# S7G7_footprint_simplified_w_ethernet_v1p.net
KiCad netlist of a schematic drawn in EAGLE
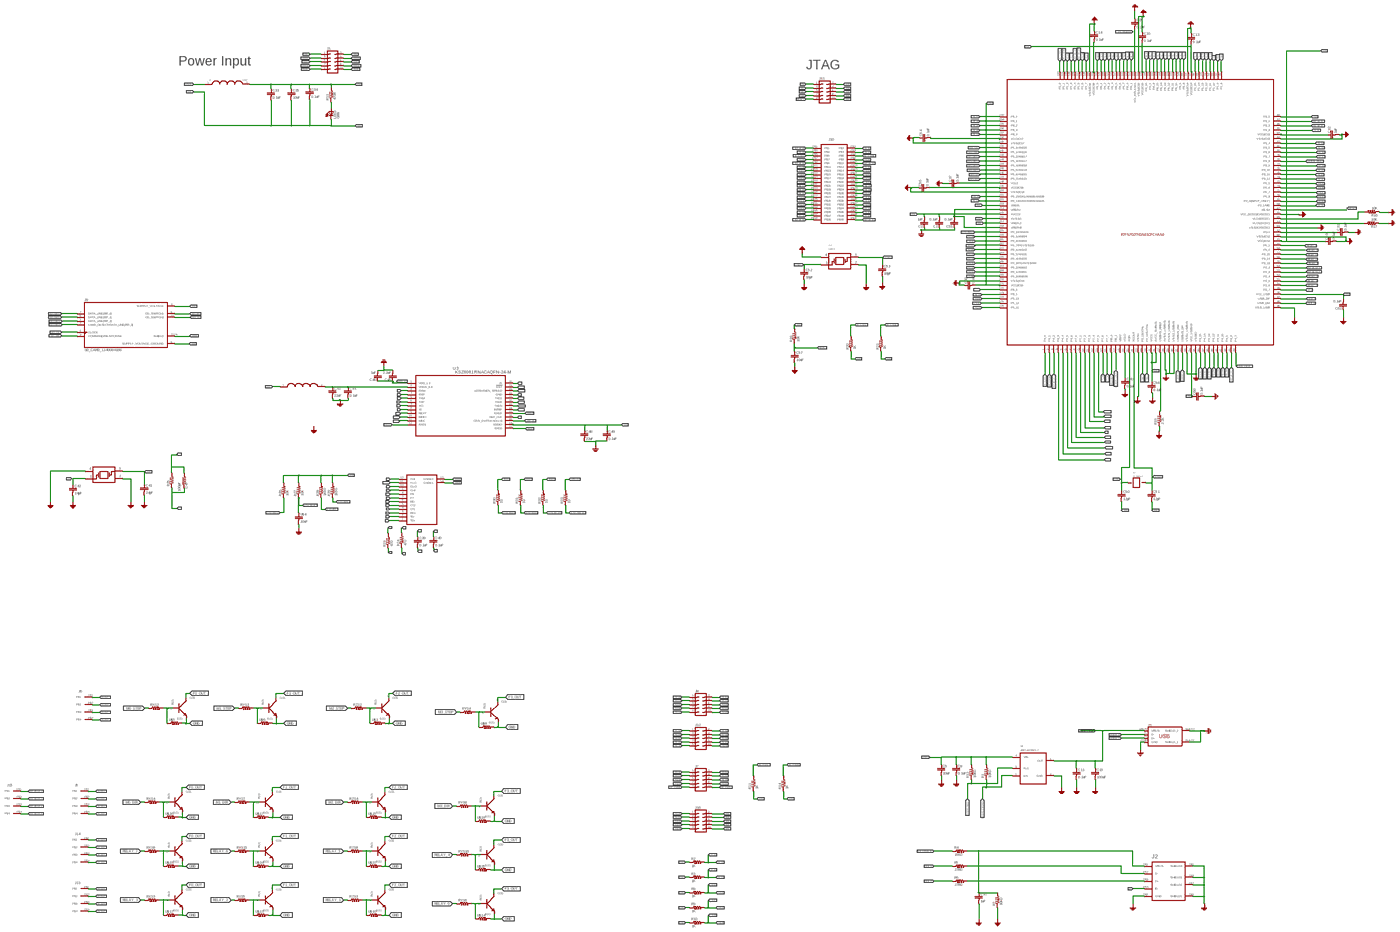
[diagram p0: schematic, sheet 1, overview]
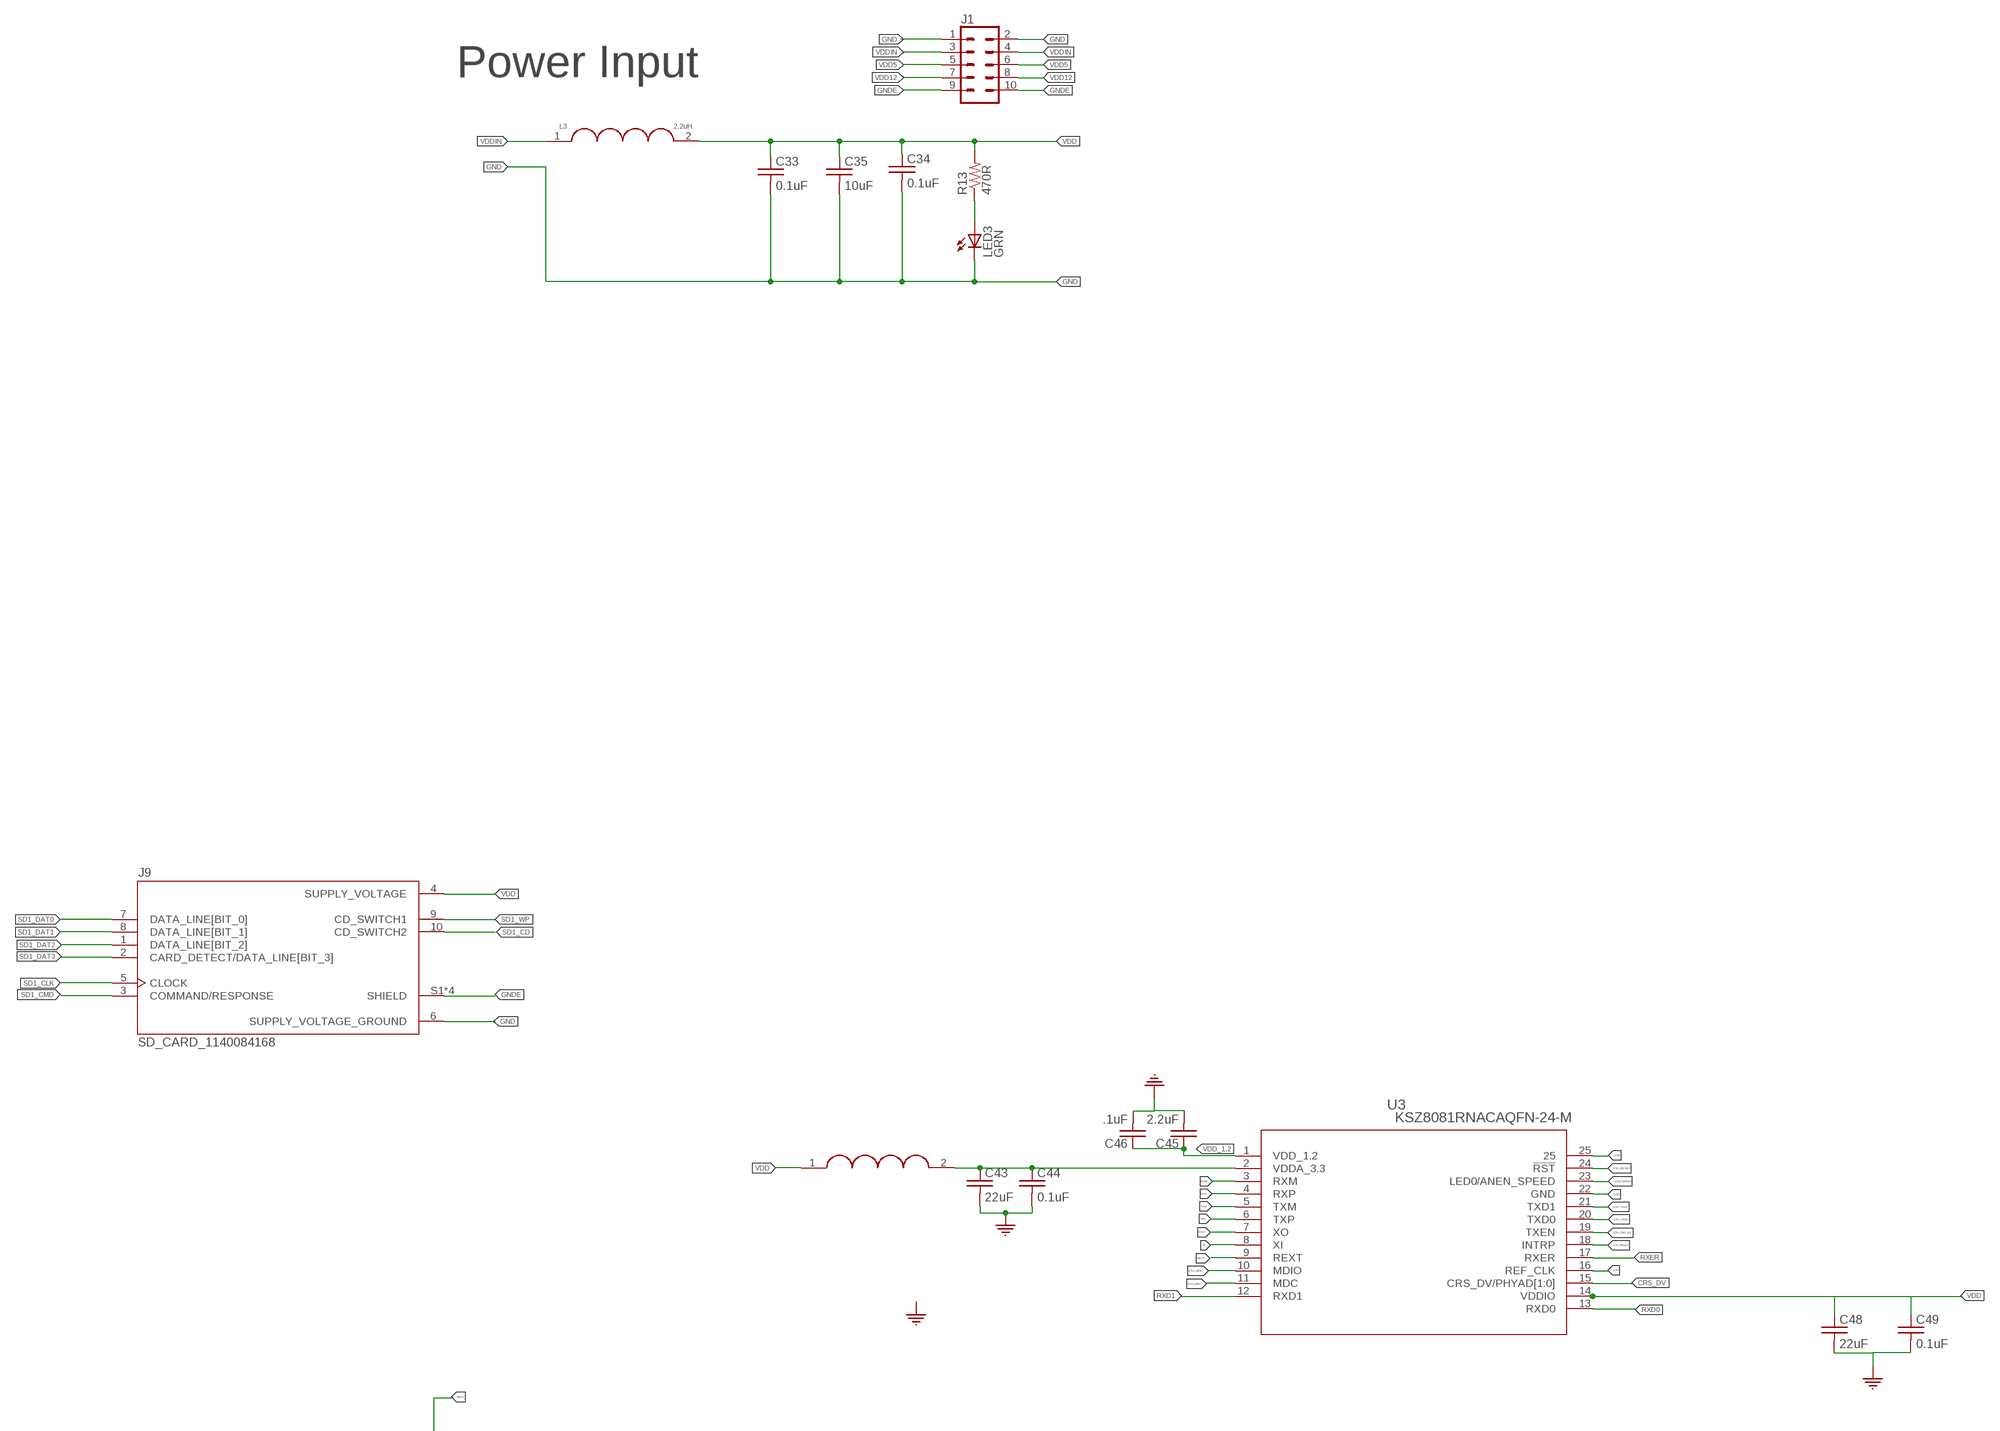
[diagram p1: schematic, sheet 1, part 1 of 4]
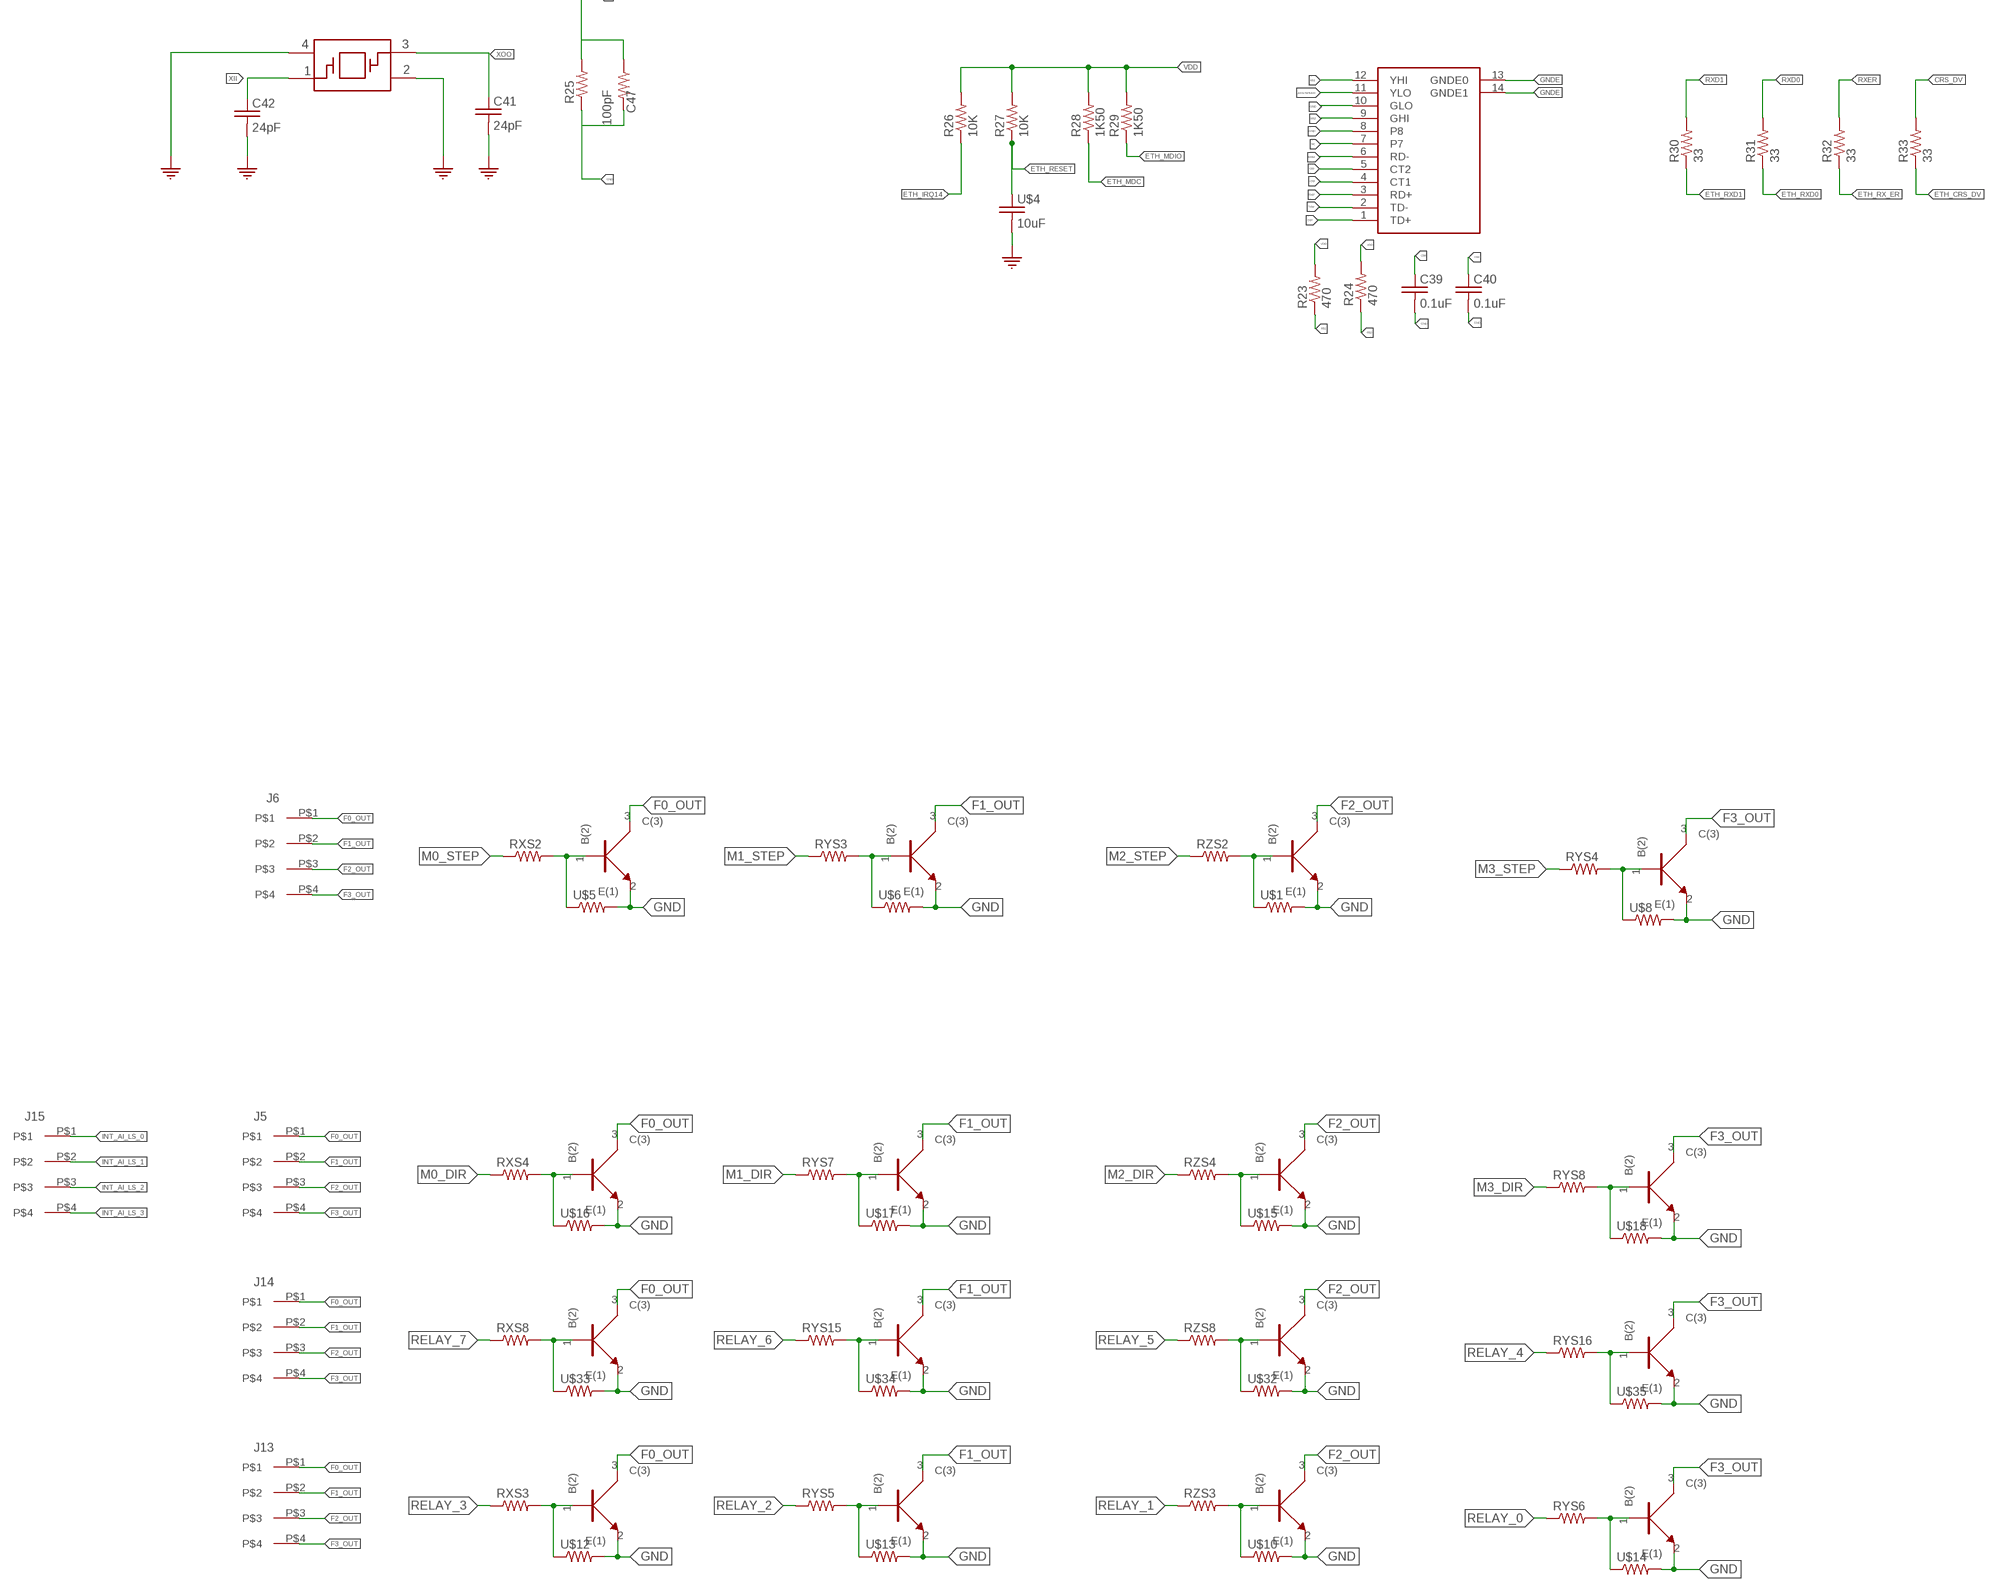
[diagram p2: schematic, sheet 1, part 2 of 4]
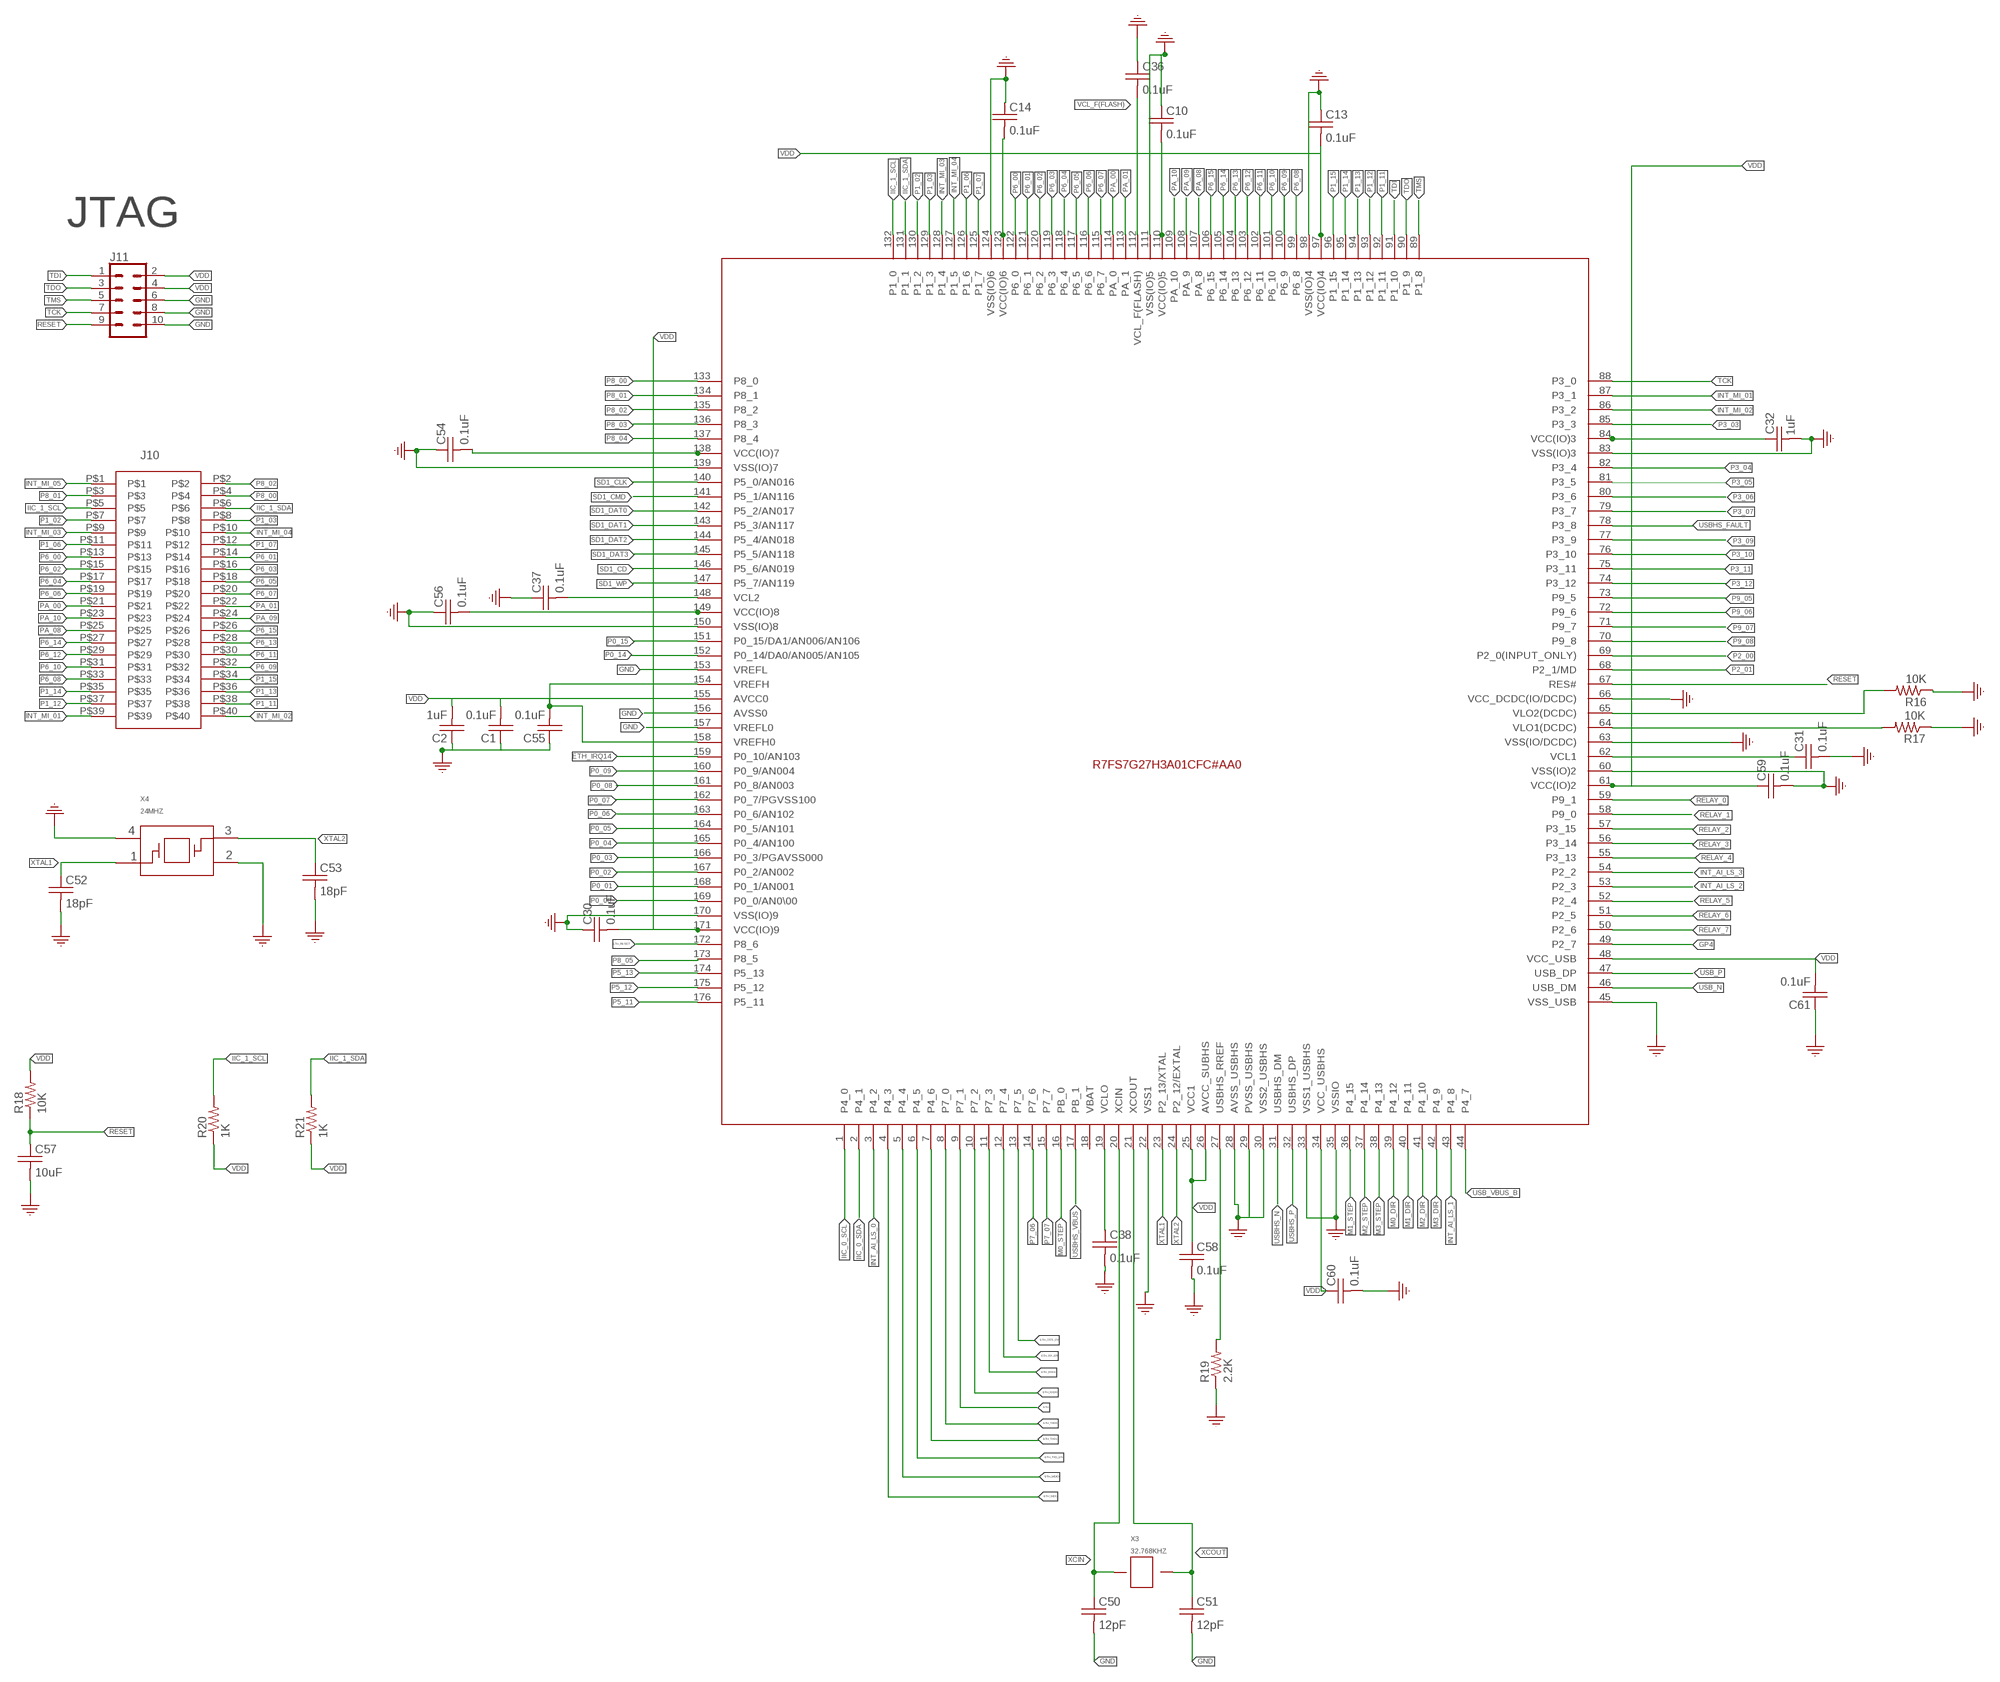
[diagram p3: schematic, sheet 1, part 3 of 4]
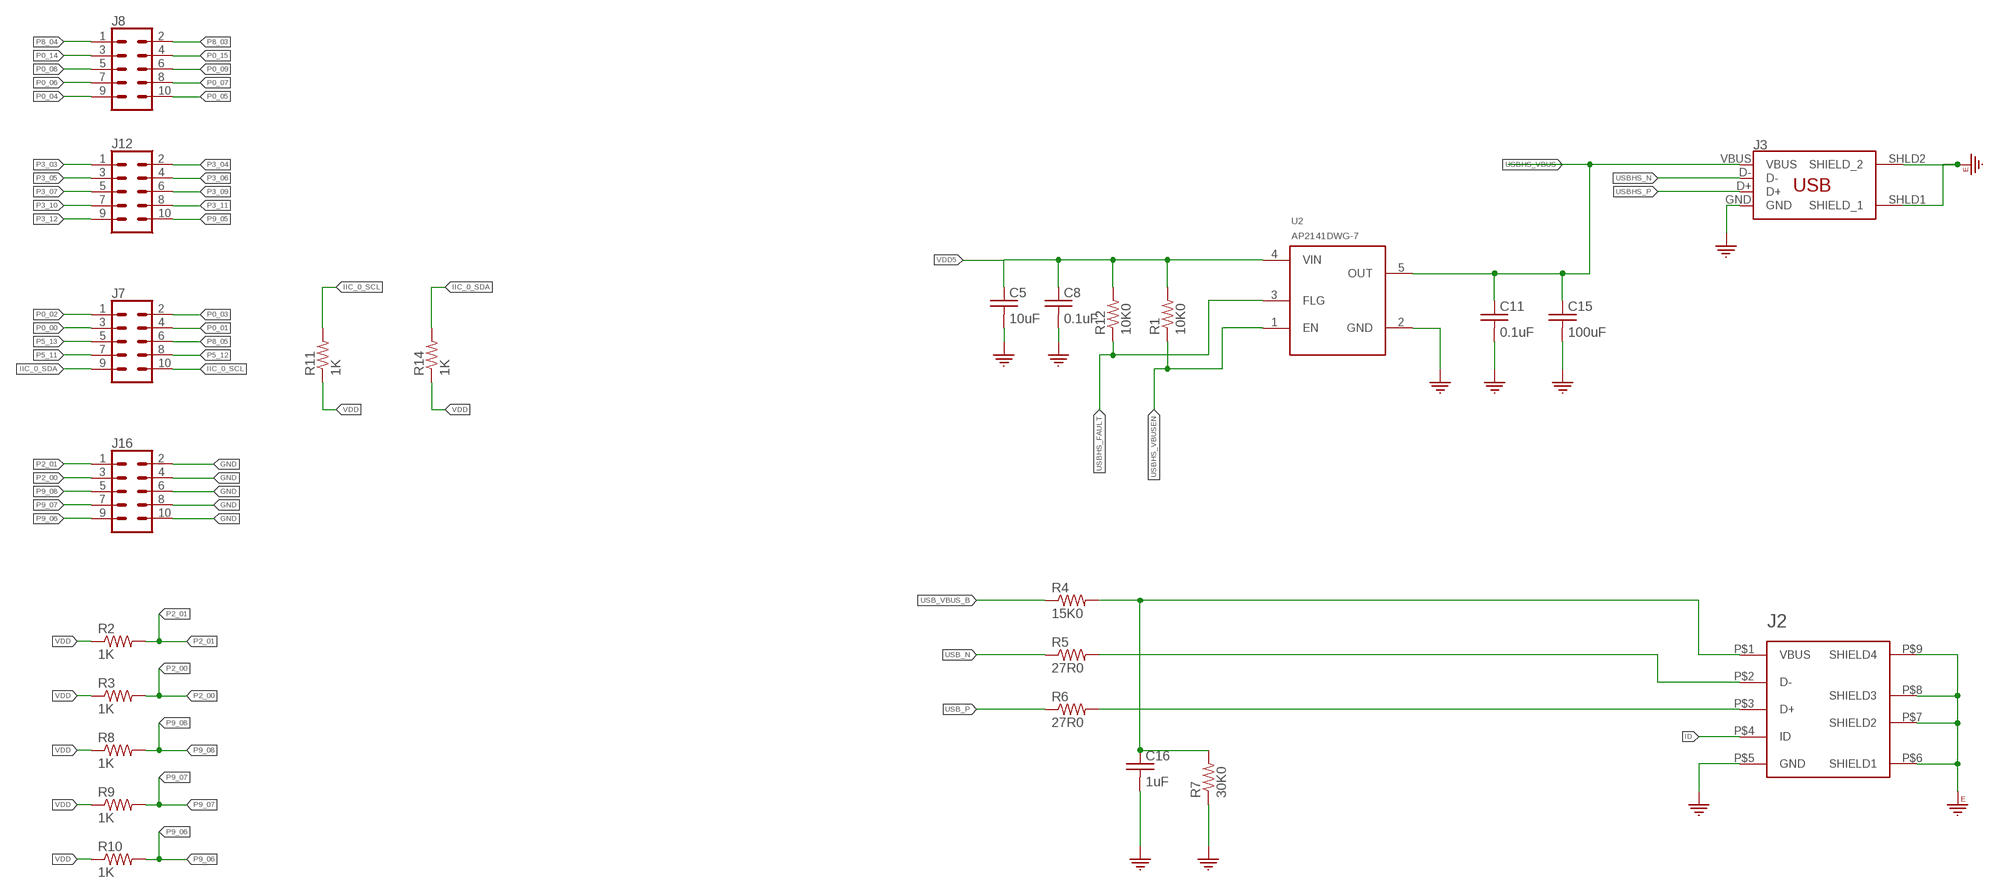
[diagram p4: schematic, sheet 1, part 4 of 4]

(export (version "E")
  (design (tool "Eeschema 10.0.6"))
  (components
    (comp (ref "C1")
      (value "0.1uF")
      (footprint "eagle-import:0402")
      (libsource (lib "eagle-import") (part "C_0402"))
    )
    (comp (ref "C2")
      (value "1uF")
      (footprint "eagle-import:0402")
      (libsource (lib "eagle-import") (part "C_0402"))
    )
    (comp (ref "C5")
      (value "10uF")
      (footprint "eagle-import:0402")
      (libsource (lib "eagle-import") (part "C_0402"))
    )
    (comp (ref "C8")
      (value "0.1uF")
      (footprint "eagle-import:0402")
      (libsource (lib "eagle-import") (part "C_0402"))
    )
    (comp (ref "C10")
      (value "0.1uF")
      (footprint "eagle-import:0402")
      (libsource (lib "eagle-import") (part "C_0402"))
    )
    (comp (ref "C11")
      (value "0.1uF")
      (footprint "eagle-import:0402")
      (libsource (lib "eagle-import") (part "C_0402"))
    )
    (comp (ref "C13")
      (value "0.1uF")
      (footprint "eagle-import:0402")
      (libsource (lib "eagle-import") (part "C_0402"))
    )
    (comp (ref "C14")
      (value "0.1uF")
      (footprint "eagle-import:0402")
      (libsource (lib "eagle-import") (part "C_0402"))
    )
    (comp (ref "C15")
      (value "100uF")
      (footprint "eagle-import:C1210")
      (libsource (lib "eagle-import") (part "C_1210"))
    )
    (comp (ref "C16")
      (value "1uF")
      (footprint "eagle-import:0402")
      (libsource (lib "eagle-import") (part "C_0402"))
    )
    (comp (ref "C30")
      (value "0.1uF")
      (footprint "eagle-import:0402")
      (libsource (lib "eagle-import") (part "C_0402"))
    )
    (comp (ref "C31")
      (value "0.1uF")
      (footprint "eagle-import:0402")
      (libsource (lib "eagle-import") (part "C_0402"))
    )
    (comp (ref "C32")
      (value "1uF")
      (footprint "eagle-import:0402")
      (libsource (lib "eagle-import") (part "C_0402"))
    )
    (comp (ref "C33")
      (value "0.1uF")
      (footprint "eagle-import:0402")
      (libsource (lib "eagle-import") (part "C_0402"))
    )
    (comp (ref "C34")
      (value "0.1uF")
      (footprint "eagle-import:0402")
      (libsource (lib "eagle-import") (part "C_0402"))
    )
    (comp (ref "C35")
      (value "10uF")
      (footprint "eagle-import:0402")
      (libsource (lib "eagle-import") (part "C_0402"))
    )
    (comp (ref "C36")
      (value "0.1uF")
      (footprint "eagle-import:0402")
      (libsource (lib "eagle-import") (part "C_0402"))
    )
    (comp (ref "C37")
      (value "0.1uF")
      (footprint "eagle-import:0402")
      (libsource (lib "eagle-import") (part "C_0402"))
    )
    (comp (ref "C38")
      (value "0.1uF")
      (footprint "eagle-import:0402")
      (libsource (lib "eagle-import") (part "C_0402"))
    )
    (comp (ref "C39")
      (value "0.1uF")
      (footprint "eagle-import:0402")
      (libsource (lib "eagle-import") (part "C_0402"))
    )
    (comp (ref "C40")
      (value "0.1uF")
      (footprint "eagle-import:0402")
      (libsource (lib "eagle-import") (part "C_0402"))
    )
    (comp (ref "C41")
      (value "24pF")
      (footprint "eagle-import:0402")
      (libsource (lib "eagle-import") (part "C_0402"))
    )
    (comp (ref "C42")
      (value "24pF")
      (footprint "eagle-import:0402")
      (libsource (lib "eagle-import") (part "C_0402"))
    )
    (comp (ref "C43")
      (value "22uF")
      (footprint "eagle-import:0603")
      (libsource (lib "eagle-import") (part "C_0603"))
    )
    (comp (ref "C44")
      (value "0.1uF")
      (footprint "eagle-import:0402")
      (libsource (lib "eagle-import") (part "C_0402"))
    )
    (comp (ref "C45")
      (value "2.2uF")
      (footprint "eagle-import:0402")
      (libsource (lib "eagle-import") (part "C_0402"))
    )
    (comp (ref "C46")
      (value ".1uF")
      (footprint "eagle-import:0402")
      (libsource (lib "eagle-import") (part "C_0402"))
    )
    (comp (ref "C47")
      (value "100pF")
      (footprint "eagle-import:0402")
      (libsource (lib "eagle-import") (part "R_0402"))
    )
    (comp (ref "C48")
      (value "22uF")
      (footprint "eagle-import:0603")
      (libsource (lib "eagle-import") (part "C_0603"))
    )
    (comp (ref "C49")
      (value "0.1uF")
      (footprint "eagle-import:0402")
      (libsource (lib "eagle-import") (part "C_0402"))
    )
    (comp (ref "C50")
      (value "12pF")
      (footprint "eagle-import:0402")
      (libsource (lib "eagle-import") (part "C_0402"))
    )
    (comp (ref "C51")
      (value "12pF")
      (footprint "eagle-import:0402")
      (libsource (lib "eagle-import") (part "C_0402"))
    )
    (comp (ref "C52")
      (value "18pF")
      (footprint "eagle-import:0402")
      (libsource (lib "eagle-import") (part "C_0402"))
    )
    (comp (ref "C53")
      (value "18pF")
      (footprint "eagle-import:0402")
      (libsource (lib "eagle-import") (part "C_0402"))
    )
    (comp (ref "C54")
      (value "0.1uF")
      (footprint "eagle-import:0402")
      (libsource (lib "eagle-import") (part "C_0402"))
    )
    (comp (ref "C55")
      (value "0.1uF")
      (footprint "eagle-import:0402")
      (libsource (lib "eagle-import") (part "C_0402"))
    )
    (comp (ref "C56")
      (value "0.1uF")
      (footprint "eagle-import:0402")
      (libsource (lib "eagle-import") (part "C_0402"))
    )
    (comp (ref "C57")
      (value "10uF")
      (footprint "eagle-import:0402")
      (libsource (lib "eagle-import") (part "C_0402"))
    )
    (comp (ref "C58")
      (value "0.1uF")
      (footprint "eagle-import:0402")
      (libsource (lib "eagle-import") (part "C_0402"))
    )
    (comp (ref "C59")
      (value "0.1uF")
      (footprint "eagle-import:0402")
      (libsource (lib "eagle-import") (part "C_0402"))
    )
    (comp (ref "C60")
      (value "0.1uF")
      (footprint "eagle-import:0402")
      (libsource (lib "eagle-import") (part "C_0402"))
    )
    (comp (ref "C61")
      (value "0.1uF")
      (footprint "eagle-import:0402")
      (libsource (lib "eagle-import") (part "C_0402"))
    )
    (comp (ref "FB2/2")
      (value "FB_0805_120_OHM")
      (footprint "eagle-import:0805")
      (libsource (lib "eagle-import") (part "FB_0805_120_OHM"))
    )
    (comp (ref "J1")
      (value "CONN_05X2PTH")
      (footprint "eagle-import:2X5")
      (libsource (lib "eagle-import") (part "CONN_05X2PTH"))
    )
    (comp (ref "J2")
      (value "USB_MICRO-B")
      (footprint "eagle-import:USB_MICRO-B")
      (libsource (lib "eagle-import") (part "USB_MICRO-B"))
    )
    (comp (ref "J3")
      (value "USB_A")
      (footprint "eagle-import:USB_A_SMT")
      (libsource (lib "eagle-import") (part "USB_A"))
    )
    (comp (ref "J4")
      (value "RJ45_WITH_ELEC")
      (footprint "eagle-import:RJ45_TH_ELEC")
      (libsource (lib "eagle-import") (part "RJ45_WITH_ELEC"))
    )
    (comp (ref "J5")
      (value "3.81MM_1_X_4_RT_ANGLE_PLUG_HEADER")
      (footprint "eagle-import:1X4_3.81MM_PITCH")
      (libsource (lib "eagle-import") (part "3.81MM_1_X_4_RT_ANGLE_PLUG_HEADER"))
    )
    (comp (ref "J6")
      (value "3.81MM_1_X_4_RT_ANGLE_PLUG_HEADER")
      (footprint "eagle-import:1X4_3.81MM_PITCH")
      (libsource (lib "eagle-import") (part "3.81MM_1_X_4_RT_ANGLE_PLUG_HEADER"))
    )
    (comp (ref "J7")
      (value "CONN_05X2NO_SILK")
      (footprint "eagle-import:2X5_NOSILK")
      (libsource (lib "eagle-import") (part "CONN_05X2NO_SILK"))
    )
    (comp (ref "J8")
      (value "CONN_05X2NO_SILK")
      (footprint "eagle-import:2X5_NOSILK")
      (libsource (lib "eagle-import") (part "CONN_05X2NO_SILK"))
    )
    (comp (ref "J9")
      (value "SD_CARD_1140084168")
      (footprint "eagle-import:AMPHENOL_1140084168")
      (fields
        (field (name "DIGI-KEY_PART_NUMBER") "114-00841-68-1-ND")
        (field (name "MF") "Amphenol ICC")
        (field (name "MP") "114-00841-68")
      )
      (libsource (lib "eagle-import") (part "SD_CARD_1140084168"))
    )
    (comp (ref "J10")
      (value "HEADER_2_X_20_GENERIC")
      (footprint "eagle-import:HEADER_2_X_20_.1_INCH")
      (libsource (lib "eagle-import") (part "HEADER_2_X_20_GENERIC"))
    )
    (comp (ref "J11")
      (value "CONN_05X2PTH")
      (footprint "eagle-import:2X5")
      (libsource (lib "eagle-import") (part "CONN_05X2PTH"))
    )
    (comp (ref "J12")
      (value "CONN_05X2NO_SILK")
      (footprint "eagle-import:2X5_NOSILK")
      (libsource (lib "eagle-import") (part "CONN_05X2NO_SILK"))
    )
    (comp (ref "J13")
      (value "3.81MM_1_X_4_RT_ANGLE_PLUG_HEADER")
      (footprint "eagle-import:1X4_3.81MM_PITCH")
      (libsource (lib "eagle-import") (part "3.81MM_1_X_4_RT_ANGLE_PLUG_HEADER"))
    )
    (comp (ref "J14")
      (value "3.81MM_1_X_4_RT_ANGLE_PLUG_HEADER")
      (footprint "eagle-import:1X4_3.81MM_PITCH")
      (libsource (lib "eagle-import") (part "3.81MM_1_X_4_RT_ANGLE_PLUG_HEADER"))
    )
    (comp (ref "J15")
      (value "3.81MM_1_X_4_RT_ANGLE_PLUG_HEADER")
      (footprint "eagle-import:1X4_3.81MM_PITCH")
      (libsource (lib "eagle-import") (part "3.81MM_1_X_4_RT_ANGLE_PLUG_HEADER"))
    )
    (comp (ref "J16")
      (value "CONN_05X2SHD_SMD")
      (footprint "eagle-import:2X5-SHROUDED_SMD")
      (libsource (lib "eagle-import") (part "CONN_05X2SHD_SMD"))
    )
    (comp (ref "L3")
      (value "2.2uH")
      (footprint "eagle-import:1008_(2520_METRIC)")
      (libsource (lib "eagle-import") (part "INDUCTOR_1008_2.2_MH_1.3A"))
    )
    (comp (ref "LED3")
      (value "LED_0805_GREEN")
      (footprint "eagle-import:LED_0805_GREEN")
      (libsource (lib "eagle-import") (part "LED_0805_GREEN"))
    )
    (comp (ref "R1")
      (value "10K0")
      (footprint "eagle-import:0402")
      (libsource (lib "eagle-import") (part "R_0402"))
    )
    (comp (ref "R2")
      (value "1K")
      (footprint "eagle-import:0402")
      (libsource (lib "eagle-import") (part "R_0402"))
    )
    (comp (ref "R3")
      (value "1K")
      (footprint "eagle-import:0402")
      (libsource (lib "eagle-import") (part "R_0402"))
    )
    (comp (ref "R4")
      (value "15K0")
      (footprint "eagle-import:0402")
      (libsource (lib "eagle-import") (part "R_0402"))
    )
    (comp (ref "R5")
      (value "27R0")
      (footprint "eagle-import:0402")
      (libsource (lib "eagle-import") (part "R_0402"))
    )
    (comp (ref "R6")
      (value "27R0")
      (footprint "eagle-import:0402")
      (libsource (lib "eagle-import") (part "R_0402"))
    )
    (comp (ref "R7")
      (value "30K0")
      (footprint "eagle-import:0402")
      (libsource (lib "eagle-import") (part "R_0402"))
    )
    (comp (ref "R8")
      (value "1K")
      (footprint "eagle-import:0402")
      (libsource (lib "eagle-import") (part "R_0402"))
    )
    (comp (ref "R9")
      (value "1K")
      (footprint "eagle-import:0402")
      (libsource (lib "eagle-import") (part "R_0402"))
    )
    (comp (ref "R10")
      (value "1K")
      (footprint "eagle-import:0402")
      (libsource (lib "eagle-import") (part "R_0402"))
    )
    (comp (ref "R11")
      (value "1K")
      (footprint "eagle-import:0402")
      (libsource (lib "eagle-import") (part "R_0402"))
    )
    (comp (ref "R12")
      (value "10K0")
      (footprint "eagle-import:0402")
      (libsource (lib "eagle-import") (part "R_0402"))
    )
    (comp (ref "R13")
      (value "470R")
      (footprint "eagle-import:0402")
      (libsource (lib "eagle-import") (part "R_0402"))
    )
    (comp (ref "R14")
      (value "1K")
      (footprint "eagle-import:0402")
      (libsource (lib "eagle-import") (part "R_0402"))
    )
    (comp (ref "R16")
      (value "10K")
      (footprint "eagle-import:0402")
      (libsource (lib "eagle-import") (part "R_0402"))
    )
    (comp (ref "R17")
      (value "10K")
      (footprint "eagle-import:0402")
      (libsource (lib "eagle-import") (part "R_0402"))
    )
    (comp (ref "R18")
      (value "10K")
      (footprint "eagle-import:0402")
      (libsource (lib "eagle-import") (part "R_0402"))
    )
    (comp (ref "R19")
      (value "2.2K")
      (footprint "eagle-import:0402")
      (libsource (lib "eagle-import") (part "R_0402"))
    )
    (comp (ref "R20")
      (value "1K")
      (footprint "eagle-import:0402")
      (libsource (lib "eagle-import") (part "R_0402"))
    )
    (comp (ref "R21")
      (value "1K")
      (footprint "eagle-import:0402")
      (libsource (lib "eagle-import") (part "R_0402"))
    )
    (comp (ref "R23")
      (value "470")
      (footprint "eagle-import:0402")
      (libsource (lib "eagle-import") (part "R_0402"))
    )
    (comp (ref "R24")
      (value "470")
      (footprint "eagle-import:0402")
      (libsource (lib "eagle-import") (part "R_0402"))
    )
    (comp (ref "R25")
      (value "6k49")
      (footprint "eagle-import:0402")
      (libsource (lib "eagle-import") (part "R_0402"))
    )
    (comp (ref "R26")
      (value "10K")
      (footprint "eagle-import:0402")
      (libsource (lib "eagle-import") (part "R_0402"))
    )
    (comp (ref "R27")
      (value "10K")
      (footprint "eagle-import:0402")
      (libsource (lib "eagle-import") (part "R_0402"))
    )
    (comp (ref "R28")
      (value "1K50")
      (footprint "eagle-import:0402")
      (libsource (lib "eagle-import") (part "R_0402"))
    )
    (comp (ref "R29")
      (value "1K50")
      (footprint "eagle-import:0402")
      (libsource (lib "eagle-import") (part "R_0402"))
    )
    (comp (ref "R30")
      (value "33")
      (footprint "eagle-import:0402")
      (libsource (lib "eagle-import") (part "R_0402"))
    )
    (comp (ref "R31")
      (value "33")
      (footprint "eagle-import:0402")
      (libsource (lib "eagle-import") (part "R_0402"))
    )
    (comp (ref "R32")
      (value "33")
      (footprint "eagle-import:0402")
      (libsource (lib "eagle-import") (part "R_0402"))
    )
    (comp (ref "R33")
      (value "33")
      (footprint "eagle-import:0402")
      (libsource (lib "eagle-import") (part "R_0402"))
    )
    (comp (ref "RXS2")
      (value "1K")
      (footprint "eagle-import:0402")
      (libsource (lib "eagle-import") (part "R_0402"))
    )
    (comp (ref "RXS3")
      (value "1K")
      (footprint "eagle-import:0402")
      (libsource (lib "eagle-import") (part "R_0402"))
    )
    (comp (ref "RXS4")
      (value "1K")
      (footprint "eagle-import:0402")
      (libsource (lib "eagle-import") (part "R_0402"))
    )
    (comp (ref "RXS8")
      (value "1K")
      (footprint "eagle-import:0402")
      (libsource (lib "eagle-import") (part "R_0402"))
    )
    (comp (ref "RYS3")
      (value "1K")
      (footprint "eagle-import:0402")
      (libsource (lib "eagle-import") (part "R_0402"))
    )
    (comp (ref "RYS4")
      (value "1K")
      (footprint "eagle-import:0402")
      (libsource (lib "eagle-import") (part "R_0402"))
    )
    (comp (ref "RYS5")
      (value "1K")
      (footprint "eagle-import:0402")
      (libsource (lib "eagle-import") (part "R_0402"))
    )
    (comp (ref "RYS6")
      (value "1K")
      (footprint "eagle-import:0402")
      (libsource (lib "eagle-import") (part "R_0402"))
    )
    (comp (ref "RYS7")
      (value "1K")
      (footprint "eagle-import:0402")
      (libsource (lib "eagle-import") (part "R_0402"))
    )
    (comp (ref "RYS8")
      (value "1K")
      (footprint "eagle-import:0402")
      (libsource (lib "eagle-import") (part "R_0402"))
    )
    (comp (ref "RYS15")
      (value "1K")
      (footprint "eagle-import:0402")
      (libsource (lib "eagle-import") (part "R_0402"))
    )
    (comp (ref "RYS16")
      (value "1K")
      (footprint "eagle-import:0402")
      (libsource (lib "eagle-import") (part "R_0402"))
    )
    (comp (ref "RZS2")
      (value "1K")
      (footprint "eagle-import:0402")
      (libsource (lib "eagle-import") (part "R_0402"))
    )
    (comp (ref "RZS3")
      (value "1K")
      (footprint "eagle-import:0402")
      (libsource (lib "eagle-import") (part "R_0402"))
    )
    (comp (ref "RZS4")
      (value "1K")
      (footprint "eagle-import:0402")
      (libsource (lib "eagle-import") (part "R_0402"))
    )
    (comp (ref "RZS8")
      (value "1K")
      (footprint "eagle-import:0402")
      (libsource (lib "eagle-import") (part "R_0402"))
    )
    (comp (ref "U$1")
      (value "1K")
      (footprint "eagle-import:0402")
      (libsource (lib "eagle-import") (part "R_0402"))
    )
    (comp (ref "U$3")
      (value "XTAL_25_MHZ")
      (footprint "eagle-import:SMD_3225")
      (libsource (lib "eagle-import") (part "XTAL_25_MHZ"))
    )
    (comp (ref "U$4")
      (value "10uF")
      (footprint "eagle-import:0402")
      (libsource (lib "eagle-import") (part "C_0402"))
    )
    (comp (ref "U$5")
      (value "1K")
      (footprint "eagle-import:0402")
      (libsource (lib "eagle-import") (part "R_0402"))
    )
    (comp (ref "U$6")
      (value "1K")
      (footprint "eagle-import:0402")
      (libsource (lib "eagle-import") (part "R_0402"))
    )
    (comp (ref "U$8")
      (value "1K")
      (footprint "eagle-import:0402")
      (libsource (lib "eagle-import") (part "R_0402"))
    )
    (comp (ref "U$10")
      (value "1K")
      (footprint "eagle-import:0402")
      (libsource (lib "eagle-import") (part "R_0402"))
    )
    (comp (ref "U$12")
      (value "1K")
      (footprint "eagle-import:0402")
      (libsource (lib "eagle-import") (part "R_0402"))
    )
    (comp (ref "U$13")
      (value "1K")
      (footprint "eagle-import:0402")
      (libsource (lib "eagle-import") (part "R_0402"))
    )
    (comp (ref "U$14")
      (value "1K")
      (footprint "eagle-import:0402")
      (libsource (lib "eagle-import") (part "R_0402"))
    )
    (comp (ref "U$15")
      (value "1K")
      (footprint "eagle-import:0402")
      (libsource (lib "eagle-import") (part "R_0402"))
    )
    (comp (ref "U$16")
      (value "1K")
      (footprint "eagle-import:0402")
      (libsource (lib "eagle-import") (part "R_0402"))
    )
    (comp (ref "U$17")
      (value "1K")
      (footprint "eagle-import:0402")
      (libsource (lib "eagle-import") (part "R_0402"))
    )
    (comp (ref "U$18")
      (value "1K")
      (footprint "eagle-import:0402")
      (libsource (lib "eagle-import") (part "R_0402"))
    )
    (comp (ref "U$32")
      (value "1K")
      (footprint "eagle-import:0402")
      (libsource (lib "eagle-import") (part "R_0402"))
    )
    (comp (ref "U$33")
      (value "1K")
      (footprint "eagle-import:0402")
      (libsource (lib "eagle-import") (part "R_0402"))
    )
    (comp (ref "U$34")
      (value "1K")
      (footprint "eagle-import:0402")
      (libsource (lib "eagle-import") (part "R_0402"))
    )
    (comp (ref "U$35")
      (value "1K")
      (footprint "eagle-import:0402")
      (libsource (lib "eagle-import") (part "R_0402"))
    )
    (comp (ref "U2")
      (value "AP2141DWG-5")
      (footprint "eagle-import:SOT-23-5")
      (libsource (lib "eagle-import") (part "AP2141DWG-5"))
    )
    (comp (ref "U3")
      (value "KSZ8081RNACAQFN-24-M")
      (footprint "eagle-import:QFN-24-M")
      (fields (field (name "MANUFACTURER_PART_NUMBER") "KSZ8081RNACA"))
      (libsource (lib "eagle-import") (part "KSZ8081RNACAQFN-24-M"))
    )
    (comp (ref "U4")
      (value "S7G2_X_176")
      (footprint "eagle-import:LQFP176_24X24")
      (libsource (lib "eagle-import") (part "S7G2_X_176"))
    )
    (comp (ref "U7")
      (value "BC846BW")
      (footprint "eagle-import:SOT323")
      (libsource (lib "eagle-import") (part "BC846BW"))
    )
    (comp (ref "U8")
      (value "BC846BW")
      (footprint "eagle-import:SOT323")
      (libsource (lib "eagle-import") (part "BC846BW"))
    )
    (comp (ref "U9")
      (value "BC846BW")
      (footprint "eagle-import:SOT323")
      (libsource (lib "eagle-import") (part "BC846BW"))
    )
    (comp (ref "U10")
      (value "BC846BW")
      (footprint "eagle-import:SOT323")
      (libsource (lib "eagle-import") (part "BC846BW"))
    )
    (comp (ref "U12")
      (value "BC846BW")
      (footprint "eagle-import:SOT323")
      (libsource (lib "eagle-import") (part "BC846BW"))
    )
    (comp (ref "U13")
      (value "BC846BW")
      (footprint "eagle-import:SOT323")
      (libsource (lib "eagle-import") (part "BC846BW"))
    )
    (comp (ref "U14")
      (value "BC846BW")
      (footprint "eagle-import:SOT323")
      (libsource (lib "eagle-import") (part "BC846BW"))
    )
    (comp (ref "U15")
      (value "BC846BW")
      (footprint "eagle-import:SOT323")
      (libsource (lib "eagle-import") (part "BC846BW"))
    )
    (comp (ref "U16")
      (value "BC846BW")
      (footprint "eagle-import:SOT323")
      (libsource (lib "eagle-import") (part "BC846BW"))
    )
    (comp (ref "U17")
      (value "BC846BW")
      (footprint "eagle-import:SOT323")
      (libsource (lib "eagle-import") (part "BC846BW"))
    )
    (comp (ref "U18")
      (value "BC846BW")
      (footprint "eagle-import:SOT323")
      (libsource (lib "eagle-import") (part "BC846BW"))
    )
    (comp (ref "U19")
      (value "BC846BW")
      (footprint "eagle-import:SOT323")
      (libsource (lib "eagle-import") (part "BC846BW"))
    )
    (comp (ref "U32")
      (value "BC846BW")
      (footprint "eagle-import:SOT323")
      (libsource (lib "eagle-import") (part "BC846BW"))
    )
    (comp (ref "U33")
      (value "BC846BW")
      (footprint "eagle-import:SOT323")
      (libsource (lib "eagle-import") (part "BC846BW"))
    )
    (comp (ref "U34")
      (value "BC846BW")
      (footprint "eagle-import:SOT323")
      (libsource (lib "eagle-import") (part "BC846BW"))
    )
    (comp (ref "U35")
      (value "BC846BW")
      (footprint "eagle-import:SOT323")
      (libsource (lib "eagle-import") (part "BC846BW"))
    )
    (comp (ref "X3")
      (value "32.768KHZ")
      (footprint "eagle-import:SMD_X_2_PADS")
      (libsource (lib "eagle-import") (part "XTAL_32.768KHZ"))
    )
    (comp (ref "X4")
      (value "24MHZ")
      (footprint "eagle-import:SMD_3225")
      (libsource (lib "eagle-import") (part "XTAL_24_MHZ"))
    )
  )
  (nets
    (net (code "1") (name "C58") (class "Default")
      (node (ref "C39") (pin "P$1") (pinfunction "1_P$1") (pintype "passive"))
      (node (ref "J4") (pin "4") (pinfunction "CT1_4") (pintype "bidirectional"))
    )
    (net (code "2") (name "C60") (class "Default")
      (node (ref "C40") (pin "P$1") (pinfunction "1_P$1") (pintype "passive"))
      (node (ref "J4") (pin "5") (pinfunction "CT2_5") (pintype "bidirectional"))
    )
    (net (code "3") (name "CRS_DV") (class "Default")
      (node (ref "R33") (pin "P$2") (pinfunction "2_P$2") (pintype "passive"))
      (node (ref "U3") (pin "15") (pinfunction "CRS_DV/PHYAD[1:0]_15") (pintype "bidirectional"))
    )
    (net (code "4") (name "ETH") (class "Default")
      (node (ref "U3") (pin "16") (pinfunction "REF_CLK_16") (pintype "bidirectional"))
      (node (ref "U4") (pin "9") (pinfunction "P7_1_9") (pintype "bidirectional"))
    )
    (net (code "5") (name "ETH_CRS_DV") (class "Default")
      (node (ref "R33") (pin "P$1") (pinfunction "1_P$1") (pintype "passive"))
      (node (ref "U4") (pin "13") (pinfunction "P7_5_13") (pintype "bidirectional"))
    )
    (net (code "6") (name "ETH_IRQ14") (class "Default")
      (node (ref "R26") (pin "P$1") (pinfunction "1_P$1") (pintype "passive"))
      (node (ref "U3") (pin "18") (pinfunction "INTRP_18") (pintype "bidirectional"))
      (node (ref "U4") (pin "159") (pinfunction "P0_10/AN103_159") (pintype "bidirectional"))
    )
    (net (code "7") (name "ETH_MDC") (class "Default")
      (node (ref "R28") (pin "P$1") (pinfunction "1_P$1") (pintype "passive"))
      (node (ref "U3") (pin "11") (pinfunction "MDC_11") (pintype "input"))
      (node (ref "U4") (pin "4") (pinfunction "P4_3_4") (pintype "bidirectional"))
    )
    (net (code "8") (name "ETH_MDIO") (class "Default")
      (node (ref "R29") (pin "P$1") (pinfunction "1_P$1") (pintype "passive"))
      (node (ref "U3") (pin "10") (pinfunction "MDIO_10") (pintype "bidirectional"))
      (node (ref "U4") (pin "5") (pinfunction "P4_4_5") (pintype "bidirectional"))
    )
    (net (code "9") (name "ETH_RESET") (class "Default")
      (node (ref "R27") (pin "P$1") (pinfunction "1_P$1") (pintype "passive"))
      (node (ref "U$4") (pin "P$1") (pinfunction "1_P$1") (pintype "passive"))
      (node (ref "U3") (pin "24") (pinfunction "~{RST}_24") (pintype "input"))
      (node (ref "U4") (pin "172") (pinfunction "P8_6_172") (pintype "bidirectional"))
    )
    (net (code "10") (name "ETH_RXD0") (class "Default")
      (node (ref "R31") (pin "P$1") (pinfunction "1_P$1") (pintype "passive"))
      (node (ref "U4") (pin "10") (pinfunction "P7_2_10") (pintype "bidirectional"))
    )
    (net (code "11") (name "ETH_RXD1") (class "Default")
      (node (ref "R30") (pin "P$1") (pinfunction "1_P$1") (pintype "passive"))
      (node (ref "U4") (pin "11") (pinfunction "P7_3_11") (pintype "bidirectional"))
    )
    (net (code "12") (name "ETH_RX_ER") (class "Default")
      (node (ref "R32") (pin "P$1") (pinfunction "1_P$1") (pintype "passive"))
      (node (ref "U4") (pin "12") (pinfunction "P7_4_12") (pintype "bidirectional"))
    )
    (net (code "13") (name "ETH_TXD0") (class "Default")
      (node (ref "U3") (pin "20") (pinfunction "TXD0_20") (pintype "input"))
      (node (ref "U4") (pin "8") (pinfunction "P7_0_8") (pintype "bidirectional"))
    )
    (net (code "14") (name "ETH_TXD1") (class "Default")
      (node (ref "U3") (pin "21") (pinfunction "TXD1_21") (pintype "bidirectional"))
      (node (ref "U4") (pin "7") (pinfunction "P4_6_7") (pintype "bidirectional"))
    )
    (net (code "15") (name "ETH_TXD_EN") (class "Default")
      (node (ref "U3") (pin "19") (pinfunction "TXEN_19") (pintype "input"))
      (node (ref "U4") (pin "6") (pinfunction "P4_5_6") (pintype "bidirectional"))
    )
    (net (code "16") (name "F0_OUT") (class "Default")
      (node (ref "J13") (pin "P$1") (pinfunction "P$1_P$1") (pintype "bidirectional"))
      (node (ref "J14") (pin "P$1") (pinfunction "P$1_P$1") (pintype "bidirectional"))
      (node (ref "J5") (pin "P$1") (pinfunction "P$1_P$1") (pintype "bidirectional"))
      (node (ref "J6") (pin "P$1") (pinfunction "P$1_P$1") (pintype "bidirectional"))
      (node (ref "U13") (pin "3") (pinfunction "C(3)_3") (pintype "input"))
      (node (ref "U17") (pin "3") (pinfunction "C(3)_3") (pintype "input"))
      (node (ref "U33") (pin "3") (pinfunction "C(3)_3") (pintype "input"))
      (node (ref "U8") (pin "3") (pinfunction "C(3)_3") (pintype "input"))
    )
    (net (code "17") (name "F1_OUT") (class "Default")
      (node (ref "J13") (pin "P$2") (pinfunction "P$2_P$2") (pintype "bidirectional"))
      (node (ref "J14") (pin "P$2") (pinfunction "P$2_P$2") (pintype "bidirectional"))
      (node (ref "J5") (pin "P$2") (pinfunction "P$2_P$2") (pintype "bidirectional"))
      (node (ref "J6") (pin "P$2") (pinfunction "P$2_P$2") (pintype "bidirectional"))
      (node (ref "U14") (pin "3") (pinfunction "C(3)_3") (pintype "input"))
      (node (ref "U18") (pin "3") (pinfunction "C(3)_3") (pintype "input"))
      (node (ref "U34") (pin "3") (pinfunction "C(3)_3") (pintype "input"))
      (node (ref "U9") (pin "3") (pinfunction "C(3)_3") (pintype "input"))
    )
    (net (code "18") (name "F2_OUT") (class "Default")
      (node (ref "J13") (pin "P$3") (pinfunction "P$3_P$3") (pintype "bidirectional"))
      (node (ref "J14") (pin "P$3") (pinfunction "P$3_P$3") (pintype "bidirectional"))
      (node (ref "J5") (pin "P$3") (pinfunction "P$3_P$3") (pintype "bidirectional"))
      (node (ref "J6") (pin "P$3") (pinfunction "P$3_P$3") (pintype "bidirectional"))
      (node (ref "U12") (pin "3") (pinfunction "C(3)_3") (pintype "input"))
      (node (ref "U16") (pin "3") (pinfunction "C(3)_3") (pintype "input"))
      (node (ref "U32") (pin "3") (pinfunction "C(3)_3") (pintype "input"))
      (node (ref "U7") (pin "3") (pinfunction "C(3)_3") (pintype "input"))
    )
    (net (code "19") (name "F3_OUT") (class "Default")
      (node (ref "J13") (pin "P$4") (pinfunction "P$4_P$4") (pintype "bidirectional"))
      (node (ref "J14") (pin "P$4") (pinfunction "P$4_P$4") (pintype "bidirectional"))
      (node (ref "J5") (pin "P$4") (pinfunction "P$4_P$4") (pintype "bidirectional"))
      (node (ref "J6") (pin "P$4") (pinfunction "P$4_P$4") (pintype "bidirectional"))
      (node (ref "U10") (pin "3") (pinfunction "C(3)_3") (pintype "input"))
      (node (ref "U15") (pin "3") (pinfunction "C(3)_3") (pintype "input"))
      (node (ref "U19") (pin "3") (pinfunction "C(3)_3") (pintype "input"))
      (node (ref "U35") (pin "3") (pinfunction "C(3)_3") (pintype "input"))
    )
    (net (code "20") (name "GND") (class "Default")
      (node (ref "C1") (pin "P$1") (pinfunction "1_P$1") (pintype "passive"))
      (node (ref "C10") (pin "P$1") (pinfunction "1_P$1") (pintype "passive"))
      (node (ref "C11") (pin "P$2") (pinfunction "2_P$2") (pintype "passive"))
      (node (ref "C13") (pin "P$1") (pinfunction "1_P$1") (pintype "passive"))
      (node (ref "C14") (pin "P$1") (pinfunction "1_P$1") (pintype "passive"))
      (node (ref "C15") (pin "2") (pinfunction "2_2") (pintype "passive"))
      (node (ref "C16") (pin "P$2") (pinfunction "2_P$2") (pintype "passive"))
      (node (ref "C2") (pin "P$1") (pinfunction "1_P$1") (pintype "passive"))
      (node (ref "C30") (pin "P$1") (pinfunction "1_P$1") (pintype "passive"))
      (node (ref "C31") (pin "P$2") (pinfunction "2_P$2") (pintype "passive"))
      (node (ref "C32") (pin "P$2") (pinfunction "2_P$2") (pintype "passive"))
      (node (ref "C33") (pin "P$2") (pinfunction "2_P$2") (pintype "passive"))
      (node (ref "C34") (pin "P$2") (pinfunction "2_P$2") (pintype "passive"))
      (node (ref "C35") (pin "P$2") (pinfunction "2_P$2") (pintype "passive"))
      (node (ref "C36") (pin "P$1") (pinfunction "1_P$1") (pintype "passive"))
      (node (ref "C37") (pin "P$1") (pinfunction "1_P$1") (pintype "passive"))
      (node (ref "C38") (pin "P$2") (pinfunction "2_P$2") (pintype "passive"))
      (node (ref "C39") (pin "P$2") (pinfunction "2_P$2") (pintype "passive"))
      (node (ref "C40") (pin "P$2") (pinfunction "2_P$2") (pintype "passive"))
      (node (ref "C41") (pin "P$2") (pinfunction "2_P$2") (pintype "passive"))
      (node (ref "C42") (pin "P$2") (pinfunction "2_P$2") (pintype "passive"))
      (node (ref "C43") (pin "2") (pinfunction "2_2") (pintype "passive"))
      (node (ref "C44") (pin "P$2") (pinfunction "2_P$2") (pintype "passive"))
      (node (ref "C45") (pin "P$2") (pinfunction "2_P$2") (pintype "passive"))
      (node (ref "C46") (pin "P$2") (pinfunction "2_P$2") (pintype "passive"))
      (node (ref "C47") (pin "P$2") (pinfunction "2_P$2") (pintype "passive"))
      (node (ref "C48") (pin "2") (pinfunction "2_2") (pintype "passive"))
      (node (ref "C49") (pin "P$2") (pinfunction "2_P$2") (pintype "passive"))
      (node (ref "C5") (pin "P$2") (pinfunction "2_P$2") (pintype "passive"))
      (node (ref "C50") (pin "P$2") (pinfunction "2_P$2") (pintype "passive"))
      (node (ref "C51") (pin "P$2") (pinfunction "2_P$2") (pintype "passive"))
      (node (ref "C52") (pin "P$2") (pinfunction "2_P$2") (pintype "passive"))
      (node (ref "C53") (pin "P$2") (pinfunction "2_P$2") (pintype "passive"))
      (node (ref "C54") (pin "P$1") (pinfunction "1_P$1") (pintype "passive"))
      (node (ref "C55") (pin "P$1") (pinfunction "1_P$1") (pintype "passive"))
      (node (ref "C56") (pin "P$1") (pinfunction "1_P$1") (pintype "passive"))
      (node (ref "C57") (pin "P$2") (pinfunction "2_P$2") (pintype "passive"))
      (node (ref "C58") (pin "P$2") (pinfunction "2_P$2") (pintype "passive"))
      (node (ref "C59") (pin "P$2") (pinfunction "2_P$2") (pintype "passive"))
      (node (ref "C60") (pin "P$2") (pinfunction "2_P$2") (pintype "passive"))
      (node (ref "C61") (pin "P$1") (pinfunction "1_P$1") (pintype "passive"))
      (node (ref "C8") (pin "P$2") (pinfunction "2_P$2") (pintype "passive"))
      (node (ref "J1") (pin "1") (pinfunction "1_1") (pintype "passive"))
      (node (ref "J1") (pin "2") (pinfunction "2_2") (pintype "passive"))
      (node (ref "J11") (pin "10") (pinfunction "10_10") (pintype "passive"))
      (node (ref "J11") (pin "6") (pinfunction "6_6") (pintype "passive"))
      (node (ref "J11") (pin "8") (pinfunction "8_8") (pintype "passive"))
      (node (ref "J16") (pin "10") (pinfunction "10_10") (pintype "passive"))
      (node (ref "J16") (pin "2") (pinfunction "2_2") (pintype "passive"))
      (node (ref "J16") (pin "4") (pinfunction "4_4") (pintype "passive"))
      (node (ref "J16") (pin "6") (pinfunction "6_6") (pintype "passive"))
      (node (ref "J16") (pin "8") (pinfunction "8_8") (pintype "passive"))
      (node (ref "J2") (pin "P$5") (pinfunction "GND_P$5") (pintype "bidirectional"))
      (node (ref "J3") (pin "GND") (pinfunction "GND_GND") (pintype "power_in"))
      (node (ref "J4") (pin "10") (pinfunction "GLO_10") (pintype "bidirectional"))
      (node (ref "J4") (pin "8") (pinfunction "P8_8") (pintype "bidirectional"))
      (node (ref "J9") (pin "6") (pinfunction "SUPPLY_VOLTAGE_GROUND_6") (pintype "power_in"))
      (node (ref "LED3") (pin "C") (pinfunction "C_C") (pintype "passive"))
      (node (ref "R16") (pin "P$1") (pinfunction "1_P$1") (pintype "passive"))
      (node (ref "R17") (pin "P$1") (pinfunction "1_P$1") (pintype "passive"))
      (node (ref "R19") (pin "P$1") (pinfunction "1_P$1") (pintype "passive"))
      (node (ref "R25") (pin "P$1") (pinfunction "1_P$1") (pintype "passive"))
      (node (ref "R7") (pin "P$1") (pinfunction "1_P$1") (pintype "passive"))
      (node (ref "U$1") (pin "P$2") (pinfunction "2_P$2") (pintype "passive"))
      (node (ref "U$10") (pin "P$2") (pinfunction "2_P$2") (pintype "passive"))
      (node (ref "U$12") (pin "P$2") (pinfunction "2_P$2") (pintype "passive"))
      (node (ref "U$13") (pin "P$2") (pinfunction "2_P$2") (pintype "passive"))
      (node (ref "U$14") (pin "P$2") (pinfunction "2_P$2") (pintype "passive"))
      (node (ref "U$15") (pin "P$2") (pinfunction "2_P$2") (pintype "passive"))
      (node (ref "U$16") (pin "P$2") (pinfunction "2_P$2") (pintype "passive"))
      (node (ref "U$17") (pin "P$2") (pinfunction "2_P$2") (pintype "passive"))
      (node (ref "U$18") (pin "P$2") (pinfunction "2_P$2") (pintype "passive"))
      (node (ref "U$3") (pin "2") (pinfunction "2_2") (pintype "bidirectional"))
      (node (ref "U$3") (pin "4") (pinfunction "4_4") (pintype "bidirectional"))
      (node (ref "U$32") (pin "P$2") (pinfunction "2_P$2") (pintype "passive"))
      (node (ref "U$33") (pin "P$2") (pinfunction "2_P$2") (pintype "passive"))
      (node (ref "U$34") (pin "P$2") (pinfunction "2_P$2") (pintype "passive"))
      (node (ref "U$35") (pin "P$2") (pinfunction "2_P$2") (pintype "passive"))
      (node (ref "U$4") (pin "P$2") (pinfunction "2_P$2") (pintype "passive"))
      (node (ref "U$5") (pin "P$2") (pinfunction "2_P$2") (pintype "passive"))
      (node (ref "U$6") (pin "P$2") (pinfunction "2_P$2") (pintype "passive"))
      (node (ref "U$8") (pin "P$2") (pinfunction "2_P$2") (pintype "passive"))
      (node (ref "U10") (pin "2") (pinfunction "E(1)_2") (pintype "output"))
      (node (ref "U12") (pin "2") (pinfunction "E(1)_2") (pintype "output"))
      (node (ref "U13") (pin "2") (pinfunction "E(1)_2") (pintype "output"))
      (node (ref "U14") (pin "2") (pinfunction "E(1)_2") (pintype "output"))
      (node (ref "U15") (pin "2") (pinfunction "E(1)_2") (pintype "output"))
      (node (ref "U16") (pin "2") (pinfunction "E(1)_2") (pintype "output"))
      (node (ref "U17") (pin "2") (pinfunction "E(1)_2") (pintype "output"))
      (node (ref "U18") (pin "2") (pinfunction "E(1)_2") (pintype "output"))
      (node (ref "U19") (pin "2") (pinfunction "E(1)_2") (pintype "output"))
      (node (ref "U2") (pin "2") (pinfunction "GND_2") (pintype "input"))
      (node (ref "U3") (pin "22") (pinfunction "GND_22") (pintype "power_in"))
      (node (ref "U3") (pin "25") (pinfunction "25_25") (pintype "passive"))
      (node (ref "U32") (pin "2") (pinfunction "E(1)_2") (pintype "output"))
      (node (ref "U33") (pin "2") (pinfunction "E(1)_2") (pintype "output"))
      (node (ref "U34") (pin "2") (pinfunction "E(1)_2") (pintype "output"))
      (node (ref "U35") (pin "2") (pinfunction "E(1)_2") (pintype "output"))
      (node (ref "U4") (pin "111") (pinfunction "VSS(IO)5_111") (pintype "bidirectional"))
      (node (ref "U4") (pin "124") (pinfunction "VSS(IO)6_124") (pintype "bidirectional"))
      (node (ref "U4") (pin "139") (pinfunction "VSS(IO)7_139") (pintype "bidirectional"))
      (node (ref "U4") (pin "150") (pinfunction "VSS(IO)8_150") (pintype "bidirectional"))
      (node (ref "U4") (pin "153") (pinfunction "VREFL_153") (pintype "bidirectional"))
      (node (ref "U4") (pin "156") (pinfunction "AVSS0_156") (pintype "bidirectional"))
      (node (ref "U4") (pin "157") (pinfunction "VREFL0_157") (pintype "bidirectional"))
      (node (ref "U4") (pin "170") (pinfunction "VSS(IO)9_170") (pintype "bidirectional"))
      (node (ref "U4") (pin "22") (pinfunction "VSS1_22") (pintype "bidirectional"))
      (node (ref "U4") (pin "28") (pinfunction "AVSS_USBHS_28") (pintype "bidirectional"))
      (node (ref "U4") (pin "29") (pinfunction "PVSS_USBHS_29") (pintype "bidirectional"))
      (node (ref "U4") (pin "30") (pinfunction "VSS2_USBHS_30") (pintype "bidirectional"))
      (node (ref "U4") (pin "33") (pinfunction "VSS1_USBHS_33") (pintype "bidirectional"))
      (node (ref "U4") (pin "35") (pinfunction "VSSIO_35") (pintype "bidirectional"))
      (node (ref "U4") (pin "45") (pinfunction "VSS_USB_45") (pintype "bidirectional"))
      (node (ref "U4") (pin "60") (pinfunction "VSS(IO)2_60") (pintype "bidirectional"))
      (node (ref "U4") (pin "63") (pinfunction "VSS(IO/DCDC)_63") (pintype "bidirectional"))
      (node (ref "U4") (pin "66") (pinfunction "VCC_DCDC(IO/DCDC)_66") (pintype "bidirectional"))
      (node (ref "U4") (pin "83") (pinfunction "VSS(IO)3_83") (pintype "bidirectional"))
      (node (ref "U4") (pin "98") (pinfunction "VSS(IO)4_98") (pintype "bidirectional"))
      (node (ref "U7") (pin "2") (pinfunction "E(1)_2") (pintype "output"))
      (node (ref "U8") (pin "2") (pinfunction "E(1)_2") (pintype "output"))
      (node (ref "U9") (pin "2") (pinfunction "E(1)_2") (pintype "output"))
      (node (ref "X4") (pin "2") (pinfunction "2_2") (pintype "bidirectional"))
      (node (ref "X4") (pin "4") (pinfunction "4_4") (pintype "bidirectional"))
    )
    (net (code "21") (name "GNDE") (class "Default")
      (node (ref "J1") (pin "10") (pinfunction "10_10") (pintype "passive"))
      (node (ref "J1") (pin "9") (pinfunction "9_9") (pintype "passive"))
      (node (ref "J2") (pin "P$6") (pinfunction "SHIELD1_P$6") (pintype "bidirectional"))
      (node (ref "J2") (pin "P$7") (pinfunction "SHIELD2_P$7") (pintype "bidirectional"))
      (node (ref "J2") (pin "P$8") (pinfunction "SHIELD3_P$8") (pintype "bidirectional"))
      (node (ref "J2") (pin "P$9") (pinfunction "SHIELD4_P$9") (pintype "bidirectional"))
      (node (ref "J3") (pin "SHLD1") (pinfunction "SHIELD_1_SHLD1") (pintype "bidirectional"))
      (node (ref "J3") (pin "SHLD2") (pinfunction "SHIELD_2_SHLD2") (pintype "bidirectional"))
      (node (ref "J4") (pin "13") (pinfunction "GNDE0_13") (pintype "bidirectional"))
      (node (ref "J4") (pin "14") (pinfunction "GNDE1_14") (pintype "bidirectional"))
      (node (ref "J9") (pin "S1") (pinfunction "SHIELD_S1") (pintype "passive"))
      (node (ref "J9") (pin "S2") (pinfunction "SHIELD_S2") (pintype "passive"))
      (node (ref "J9") (pin "S3") (pinfunction "SHIELD_S3") (pintype "passive"))
      (node (ref "J9") (pin "S4") (pinfunction "SHIELD_S4") (pintype "passive"))
    )
    (net (code "22") (name "GP4") (class "Default")
      (node (ref "U4") (pin "49") (pinfunction "P2_7_49") (pintype "bidirectional"))
    )
    (net (code "23") (name "ID") (class "Default")
      (node (ref "J2") (pin "P$4") (pinfunction "ID_P$4") (pintype "bidirectional"))
    )
    (net (code "24") (name "IIC_0_SCL") (class "Default")
      (node (ref "J7") (pin "10") (pinfunction "10_10") (pintype "passive"))
      (node (ref "R11") (pin "P$2") (pinfunction "2_P$2") (pintype "passive"))
      (node (ref "U4") (pin "1") (pinfunction "P4_0_1") (pintype "bidirectional"))
    )
    (net (code "25") (name "IIC_0_SDA") (class "Default")
      (node (ref "J7") (pin "9") (pinfunction "9_9") (pintype "passive"))
      (node (ref "R14") (pin "P$2") (pinfunction "2_P$2") (pintype "passive"))
      (node (ref "U4") (pin "2") (pinfunction "P4_1_2") (pintype "bidirectional"))
    )
    (net (code "26") (name "IIC_1_SCL") (class "Default")
      (node (ref "J10") (pin "P$5") (pinfunction "P$5_P$5") (pintype "bidirectional"))
      (node (ref "R20") (pin "P$2") (pinfunction "2_P$2") (pintype "passive"))
      (node (ref "U4") (pin "132") (pinfunction "P1_0_132") (pintype "bidirectional"))
    )
    (net (code "27") (name "IIC_1_SDA") (class "Default")
      (node (ref "J10") (pin "P$6") (pinfunction "P$6_P$6") (pintype "bidirectional"))
      (node (ref "R21") (pin "P$2") (pinfunction "2_P$2") (pintype "passive"))
      (node (ref "U4") (pin "131") (pinfunction "P1_1_131") (pintype "bidirectional"))
    )
    (net (code "28") (name "INT_AI_LS_0") (class "Default")
      (node (ref "J15") (pin "P$1") (pinfunction "P$1_P$1") (pintype "bidirectional"))
      (node (ref "U4") (pin "3") (pinfunction "P4_2_3") (pintype "bidirectional"))
    )
    (net (code "29") (name "INT_AI_LS_1") (class "Default")
      (node (ref "J15") (pin "P$2") (pinfunction "P$2_P$2") (pintype "bidirectional"))
      (node (ref "U4") (pin "43") (pinfunction "P4_8_43") (pintype "bidirectional"))
    )
    (net (code "30") (name "INT_AI_LS_2") (class "Default")
      (node (ref "J15") (pin "P$3") (pinfunction "P$3_P$3") (pintype "bidirectional"))
      (node (ref "U4") (pin "53") (pinfunction "P2_3_53") (pintype "bidirectional"))
    )
    (net (code "31") (name "INT_AI_LS_3") (class "Default")
      (node (ref "J15") (pin "P$4") (pinfunction "P$4_P$4") (pintype "bidirectional"))
      (node (ref "U4") (pin "54") (pinfunction "P2_2_54") (pintype "bidirectional"))
    )
    (net (code "32") (name "INT_MI_01") (class "Default")
      (node (ref "J10") (pin "P$39") (pinfunction "P$39_P$39") (pintype "bidirectional"))
      (node (ref "U4") (pin "87") (pinfunction "P3_1_87") (pintype "bidirectional"))
    )
    (net (code "33") (name "INT_MI_02") (class "Default")
      (node (ref "J10") (pin "P$40") (pinfunction "P$40_P$40") (pintype "bidirectional"))
      (node (ref "U4") (pin "86") (pinfunction "P3_2_86") (pintype "bidirectional"))
    )
    (net (code "34") (name "INT_MI_03") (class "Default")
      (node (ref "J10") (pin "P$9") (pinfunction "P$9_P$9") (pintype "bidirectional"))
      (node (ref "U4") (pin "128") (pinfunction "P1_4_128") (pintype "bidirectional"))
    )
    (net (code "35") (name "INT_MI_04") (class "Default")
      (node (ref "J10") (pin "P$10") (pinfunction "P$10_P$10") (pintype "bidirectional"))
      (node (ref "U4") (pin "127") (pinfunction "P1_5_127") (pintype "bidirectional"))
    )
    (net (code "36") (name "INT_MI_05") (class "Default")
      (node (ref "J10") (pin "P$1") (pinfunction "P$1_P$1") (pintype "bidirectional"))
    )
    (net (code "37") (name "LED1{slash}SPEED") (class "Default")
      (node (ref "J4") (pin "11") (pinfunction "YLO_11") (pintype "bidirectional"))
      (node (ref "U3") (pin "23") (pinfunction "LED0/ANEN_SPEED_23") (pintype "bidirectional"))
    )
    (net (code "38") (name "M0_DIR") (class "Default")
      (node (ref "RXS4") (pin "P$1") (pinfunction "1_P$1") (pintype "passive"))
      (node (ref "U4") (pin "39") (pinfunction "P4_12_39") (pintype "bidirectional"))
    )
    (net (code "39") (name "M0_STEP") (class "Default")
      (node (ref "RXS2") (pin "P$1") (pinfunction "1_P$1") (pintype "passive"))
      (node (ref "U4") (pin "16") (pinfunction "PB_0_16") (pintype "bidirectional"))
    )
    (net (code "40") (name "M1_DIR") (class "Default")
      (node (ref "RYS7") (pin "P$1") (pinfunction "1_P$1") (pintype "passive"))
      (node (ref "U4") (pin "40") (pinfunction "P4_11_40") (pintype "bidirectional"))
    )
    (net (code "41") (name "M1_STEP") (class "Default")
      (node (ref "RYS3") (pin "P$1") (pinfunction "1_P$1") (pintype "passive"))
      (node (ref "U4") (pin "36") (pinfunction "P4_15_36") (pintype "bidirectional"))
    )
    (net (code "42") (name "M2_DIR") (class "Default")
      (node (ref "RZS4") (pin "P$1") (pinfunction "1_P$1") (pintype "passive"))
      (node (ref "U4") (pin "41") (pinfunction "P4_10_41") (pintype "bidirectional"))
    )
    (net (code "43") (name "M2_STEP") (class "Default")
      (node (ref "RZS2") (pin "P$1") (pinfunction "1_P$1") (pintype "passive"))
      (node (ref "U4") (pin "37") (pinfunction "P4_14_37") (pintype "bidirectional"))
    )
    (net (code "44") (name "M3_DIR") (class "Default")
      (node (ref "RYS8") (pin "P$1") (pinfunction "1_P$1") (pintype "passive"))
      (node (ref "U4") (pin "42") (pinfunction "P4_9_42") (pintype "bidirectional"))
    )
    (net (code "45") (name "M3_STEP") (class "Default")
      (node (ref "RYS4") (pin "P$1") (pinfunction "1_P$1") (pintype "passive"))
      (node (ref "U4") (pin "38") (pinfunction "P4_13_38") (pintype "bidirectional"))
    )
    (net (code "46") (name "NC") (class "Default")
      (node (ref "J4") (pin "7") (pinfunction "P7_7") (pintype "bidirectional"))
    )
    (net (code "47") (name "Net-(C16-1)") (class "Default")
      (node (ref "C16") (pin "P$1") (pinfunction "1_P$1") (pintype "passive"))
      (node (ref "J2") (pin "P$1") (pinfunction "VBUS_P$1") (pintype "bidirectional"))
      (node (ref "R4") (pin "P$2") (pinfunction "2_P$2") (pintype "passive"))
      (node (ref "R7") (pin "P$2") (pinfunction "2_P$2") (pintype "passive"))
    )
    (net (code "48") (name "Net-(C31-1)") (class "Default")
      (node (ref "C31") (pin "P$1") (pinfunction "1_P$1") (pintype "passive"))
      (node (ref "U4") (pin "62") (pinfunction "VCL1_62") (pintype "bidirectional"))
    )
    (net (code "49") (name "Net-(C37-2)") (class "Default")
      (node (ref "C37") (pin "P$2") (pinfunction "2_P$2") (pintype "passive"))
      (node (ref "U4") (pin "148") (pinfunction "VCL2_148") (pintype "bidirectional"))
    )
    (net (code "50") (name "Net-(C38-1)") (class "Default")
      (node (ref "C38") (pin "P$1") (pinfunction "1_P$1") (pintype "passive"))
      (node (ref "U4") (pin "19") (pinfunction "VCLO_19") (pintype "bidirectional"))
    )
    (net (code "51") (name "Net-(C44-1)") (class "Default")
      (node (ref "C43") (pin "1") (pinfunction "1_1") (pintype "passive"))
      (node (ref "C44") (pin "P$1") (pinfunction "1_P$1") (pintype "passive"))
      (node (ref "FB2/2") (pin "2") (pinfunction "P$2_2") (pintype "bidirectional"))
      (node (ref "U3") (pin "2") (pinfunction "VDDA_3.3_2") (pintype "power_in"))
    )
    (net (code "52") (name "Net-(J2-D+)") (class "Default")
      (node (ref "J2") (pin "P$3") (pinfunction "D+_P$3") (pintype "bidirectional"))
      (node (ref "R6") (pin "P$2") (pinfunction "2_P$2") (pintype "passive"))
    )
    (net (code "53") (name "Net-(J2-D-)") (class "Default")
      (node (ref "J2") (pin "P$2") (pinfunction "D-_P$2") (pintype "bidirectional"))
      (node (ref "R5") (pin "P$2") (pinfunction "2_P$2") (pintype "passive"))
    )
    (net (code "54") (name "Net-(R13-1)") (class "Default")
      (node (ref "LED3") (pin "A") (pinfunction "A_A") (pintype "passive"))
      (node (ref "R13") (pin "P$1") (pinfunction "1_P$1") (pintype "passive"))
    )
    (net (code "55") (name "Net-(R16-2)") (class "Default")
      (node (ref "R16") (pin "P$2") (pinfunction "2_P$2") (pintype "passive"))
      (node (ref "U4") (pin "65") (pinfunction "VLO2(DCDC)_65") (pintype "bidirectional"))
    )
    (net (code "56") (name "Net-(R17-2)") (class "Default")
      (node (ref "R17") (pin "P$2") (pinfunction "2_P$2") (pintype "passive"))
      (node (ref "U4") (pin "64") (pinfunction "VLO1(DCDC)_64") (pintype "bidirectional"))
    )
    (net (code "57") (name "Net-(R19-2)") (class "Default")
      (node (ref "R19") (pin "P$2") (pinfunction "2_P$2") (pintype "passive"))
      (node (ref "U4") (pin "27") (pinfunction "USBHS_RREF_27") (pintype "bidirectional"))
    )
    (net (code "58") (name "Net-(RXS2-2)") (class "Default")
      (node (ref "RXS2") (pin "P$2") (pinfunction "2_P$2") (pintype "passive"))
      (node (ref "U$5") (pin "P$1") (pinfunction "1_P$1") (pintype "passive"))
      (node (ref "U8") (pin "1") (pinfunction "B(2)_1") (pintype "input"))
    )
    (net (code "59") (name "Net-(RXS3-2)") (class "Default")
      (node (ref "RXS3") (pin "P$2") (pinfunction "2_P$2") (pintype "passive"))
      (node (ref "U$12") (pin "P$1") (pinfunction "1_P$1") (pintype "passive"))
      (node (ref "U13") (pin "1") (pinfunction "B(2)_1") (pintype "input"))
    )
    (net (code "60") (name "Net-(RXS4-2)") (class "Default")
      (node (ref "RXS4") (pin "P$2") (pinfunction "2_P$2") (pintype "passive"))
      (node (ref "U$16") (pin "P$1") (pinfunction "1_P$1") (pintype "passive"))
      (node (ref "U17") (pin "1") (pinfunction "B(2)_1") (pintype "input"))
    )
    (net (code "61") (name "Net-(RXS8-2)") (class "Default")
      (node (ref "RXS8") (pin "P$2") (pinfunction "2_P$2") (pintype "passive"))
      (node (ref "U$33") (pin "P$1") (pinfunction "1_P$1") (pintype "passive"))
      (node (ref "U33") (pin "1") (pinfunction "B(2)_1") (pintype "input"))
    )
    (net (code "62") (name "Net-(RYS3-2)") (class "Default")
      (node (ref "RYS3") (pin "P$2") (pinfunction "2_P$2") (pintype "passive"))
      (node (ref "U$6") (pin "P$1") (pinfunction "1_P$1") (pintype "passive"))
      (node (ref "U9") (pin "1") (pinfunction "B(2)_1") (pintype "input"))
    )
    (net (code "63") (name "Net-(RYS4-2)") (class "Default")
      (node (ref "RYS4") (pin "P$2") (pinfunction "2_P$2") (pintype "passive"))
      (node (ref "U$8") (pin "P$1") (pinfunction "1_P$1") (pintype "passive"))
      (node (ref "U10") (pin "1") (pinfunction "B(2)_1") (pintype "input"))
    )
    (net (code "64") (name "Net-(RYS5-2)") (class "Default")
      (node (ref "RYS5") (pin "P$2") (pinfunction "2_P$2") (pintype "passive"))
      (node (ref "U$13") (pin "P$1") (pinfunction "1_P$1") (pintype "passive"))
      (node (ref "U14") (pin "1") (pinfunction "B(2)_1") (pintype "input"))
    )
    (net (code "65") (name "Net-(RYS6-2)") (class "Default")
      (node (ref "RYS6") (pin "P$2") (pinfunction "2_P$2") (pintype "passive"))
      (node (ref "U$14") (pin "P$1") (pinfunction "1_P$1") (pintype "passive"))
      (node (ref "U15") (pin "1") (pinfunction "B(2)_1") (pintype "input"))
    )
    (net (code "66") (name "Net-(RYS7-2)") (class "Default")
      (node (ref "RYS7") (pin "P$2") (pinfunction "2_P$2") (pintype "passive"))
      (node (ref "U$17") (pin "P$1") (pinfunction "1_P$1") (pintype "passive"))
      (node (ref "U18") (pin "1") (pinfunction "B(2)_1") (pintype "input"))
    )
    (net (code "67") (name "Net-(RYS8-2)") (class "Default")
      (node (ref "RYS8") (pin "P$2") (pinfunction "2_P$2") (pintype "passive"))
      (node (ref "U$18") (pin "P$1") (pinfunction "1_P$1") (pintype "passive"))
      (node (ref "U19") (pin "1") (pinfunction "B(2)_1") (pintype "input"))
    )
    (net (code "68") (name "Net-(RYS15-2)") (class "Default")
      (node (ref "RYS15") (pin "P$2") (pinfunction "2_P$2") (pintype "passive"))
      (node (ref "U$34") (pin "P$1") (pinfunction "1_P$1") (pintype "passive"))
      (node (ref "U34") (pin "1") (pinfunction "B(2)_1") (pintype "input"))
    )
    (net (code "69") (name "Net-(RYS16-2)") (class "Default")
      (node (ref "RYS16") (pin "P$2") (pinfunction "2_P$2") (pintype "passive"))
      (node (ref "U$35") (pin "P$1") (pinfunction "1_P$1") (pintype "passive"))
      (node (ref "U35") (pin "1") (pinfunction "B(2)_1") (pintype "input"))
    )
    (net (code "70") (name "Net-(RZS2-2)") (class "Default")
      (node (ref "RZS2") (pin "P$2") (pinfunction "2_P$2") (pintype "passive"))
      (node (ref "U$1") (pin "P$1") (pinfunction "1_P$1") (pintype "passive"))
      (node (ref "U7") (pin "1") (pinfunction "B(2)_1") (pintype "input"))
    )
    (net (code "71") (name "Net-(RZS3-2)") (class "Default")
      (node (ref "RZS3") (pin "P$2") (pinfunction "2_P$2") (pintype "passive"))
      (node (ref "U$10") (pin "P$1") (pinfunction "1_P$1") (pintype "passive"))
      (node (ref "U12") (pin "1") (pinfunction "B(2)_1") (pintype "input"))
    )
    (net (code "72") (name "Net-(RZS4-2)") (class "Default")
      (node (ref "RZS4") (pin "P$2") (pinfunction "2_P$2") (pintype "passive"))
      (node (ref "U$15") (pin "P$1") (pinfunction "1_P$1") (pintype "passive"))
      (node (ref "U16") (pin "1") (pinfunction "B(2)_1") (pintype "input"))
    )
    (net (code "73") (name "Net-(RZS8-2)") (class "Default")
      (node (ref "RZS8") (pin "P$2") (pinfunction "2_P$2") (pintype "passive"))
      (node (ref "U$32") (pin "P$1") (pinfunction "1_P$1") (pintype "passive"))
      (node (ref "U32") (pin "1") (pinfunction "B(2)_1") (pintype "input"))
    )
    (net (code "74") (name "P0_00") (class "Default")
      (node (ref "J7") (pin "3") (pinfunction "3_3") (pintype "passive"))
      (node (ref "U4") (pin "169") (pinfunction "P0_0/AN0\\00_169") (pintype "bidirectional"))
    )
    (net (code "75") (name "P0_01") (class "Default")
      (node (ref "J7") (pin "4") (pinfunction "4_4") (pintype "passive"))
      (node (ref "U4") (pin "168") (pinfunction "P0_1/AN001_168") (pintype "bidirectional"))
    )
    (net (code "76") (name "P0_02") (class "Default")
      (node (ref "J7") (pin "1") (pinfunction "1_1") (pintype "passive"))
      (node (ref "U4") (pin "167") (pinfunction "P0_2/AN002_167") (pintype "bidirectional"))
    )
    (net (code "77") (name "P0_03") (class "Default")
      (node (ref "J7") (pin "2") (pinfunction "2_2") (pintype "passive"))
      (node (ref "U4") (pin "166") (pinfunction "P0_3/PGAVSS000_166") (pintype "bidirectional"))
    )
    (net (code "78") (name "P0_04") (class "Default")
      (node (ref "J8") (pin "9") (pinfunction "9_9") (pintype "passive"))
      (node (ref "U4") (pin "165") (pinfunction "P0_4/AN100_165") (pintype "bidirectional"))
    )
    (net (code "79") (name "P0_05") (class "Default")
      (node (ref "J8") (pin "10") (pinfunction "10_10") (pintype "passive"))
      (node (ref "U4") (pin "164") (pinfunction "P0_5/AN101_164") (pintype "bidirectional"))
    )
    (net (code "80") (name "P0_06") (class "Default")
      (node (ref "J8") (pin "7") (pinfunction "7_7") (pintype "passive"))
      (node (ref "U4") (pin "163") (pinfunction "P0_6/AN102_163") (pintype "bidirectional"))
    )
    (net (code "81") (name "P0_07") (class "Default")
      (node (ref "J8") (pin "8") (pinfunction "8_8") (pintype "passive"))
      (node (ref "U4") (pin "162") (pinfunction "P0_7/PGVSS100_162") (pintype "bidirectional"))
    )
    (net (code "82") (name "P0_08") (class "Default")
      (node (ref "J8") (pin "5") (pinfunction "5_5") (pintype "passive"))
      (node (ref "U4") (pin "161") (pinfunction "P0_8/AN003_161") (pintype "bidirectional"))
    )
    (net (code "83") (name "P0_09") (class "Default")
      (node (ref "J8") (pin "6") (pinfunction "6_6") (pintype "passive"))
      (node (ref "U4") (pin "160") (pinfunction "P0_9/AN004_160") (pintype "bidirectional"))
    )
    (net (code "84") (name "P0_14") (class "Default")
      (node (ref "J8") (pin "3") (pinfunction "3_3") (pintype "passive"))
      (node (ref "U4") (pin "152") (pinfunction "P0_14/DA0/AN005/AN105_152") (pintype "bidirectional"))
    )
    (net (code "85") (name "P0_15") (class "Default")
      (node (ref "J8") (pin "4") (pinfunction "4_4") (pintype "passive"))
      (node (ref "U4") (pin "151") (pinfunction "P0_15/DA1/AN006/AN106_151") (pintype "bidirectional"))
    )
    (net (code "86") (name "P1_02") (class "Default")
      (node (ref "J10") (pin "P$7") (pinfunction "P$7_P$7") (pintype "bidirectional"))
      (node (ref "U4") (pin "130") (pinfunction "P1_2_130") (pintype "bidirectional"))
    )
    (net (code "87") (name "P1_03") (class "Default")
      (node (ref "J10") (pin "P$8") (pinfunction "P$8_P$8") (pintype "bidirectional"))
      (node (ref "U4") (pin "129") (pinfunction "P1_3_129") (pintype "bidirectional"))
    )
    (net (code "88") (name "P1_06") (class "Default")
      (node (ref "J10") (pin "P$11") (pinfunction "P$11_P$11") (pintype "bidirectional"))
      (node (ref "U4") (pin "126") (pinfunction "P1_6_126") (pintype "bidirectional"))
    )
    (net (code "89") (name "P1_07") (class "Default")
      (node (ref "J10") (pin "P$12") (pinfunction "P$12_P$12") (pintype "bidirectional"))
      (node (ref "U4") (pin "125") (pinfunction "P1_7_125") (pintype "bidirectional"))
    )
    (net (code "90") (name "P1_11") (class "Default")
      (node (ref "J10") (pin "P$38") (pinfunction "P$38_P$38") (pintype "bidirectional"))
      (node (ref "U4") (pin "92") (pinfunction "P1_11_92") (pintype "bidirectional"))
    )
    (net (code "91") (name "P1_12") (class "Default")
      (node (ref "J10") (pin "P$37") (pinfunction "P$37_P$37") (pintype "bidirectional"))
      (node (ref "U4") (pin "93") (pinfunction "P1_12_93") (pintype "bidirectional"))
    )
    (net (code "92") (name "P1_13") (class "Default")
      (node (ref "J10") (pin "P$36") (pinfunction "P$36_P$36") (pintype "bidirectional"))
      (node (ref "U4") (pin "94") (pinfunction "P1_13_94") (pintype "bidirectional"))
    )
    (net (code "93") (name "P1_14") (class "Default")
      (node (ref "J10") (pin "P$35") (pinfunction "P$35_P$35") (pintype "bidirectional"))
      (node (ref "U4") (pin "95") (pinfunction "P1_14_95") (pintype "bidirectional"))
    )
    (net (code "94") (name "P1_15") (class "Default")
      (node (ref "J10") (pin "P$34") (pinfunction "P$34_P$34") (pintype "bidirectional"))
      (node (ref "U4") (pin "96") (pinfunction "P1_15_96") (pintype "bidirectional"))
    )
    (net (code "95") (name "P2_00") (class "Default")
      (node (ref "J16") (pin "3") (pinfunction "3_3") (pintype "passive"))
      (node (ref "R3") (pin "P$2") (pinfunction "2_P$2") (pintype "passive"))
      (node (ref "U4") (pin "69") (pinfunction "P2_0(INPUT_ONLY)_69") (pintype "bidirectional"))
    )
    (net (code "96") (name "P2_01") (class "Default")
      (node (ref "J16") (pin "1") (pinfunction "1_1") (pintype "passive"))
      (node (ref "R2") (pin "P$2") (pinfunction "2_P$2") (pintype "passive"))
      (node (ref "U4") (pin "68") (pinfunction "P2_1/MD_68") (pintype "bidirectional"))
    )
    (net (code "97") (name "P3_03") (class "Default")
      (node (ref "J12") (pin "1") (pinfunction "1_1") (pintype "passive"))
      (node (ref "U4") (pin "85") (pinfunction "P3_3_85") (pintype "bidirectional"))
    )
    (net (code "98") (name "P3_04") (class "Default")
      (node (ref "J12") (pin "2") (pinfunction "2_2") (pintype "passive"))
      (node (ref "U4") (pin "82") (pinfunction "P3_4_82") (pintype "bidirectional"))
    )
    (net (code "99") (name "P3_05") (class "Default")
      (node (ref "J12") (pin "3") (pinfunction "3_3") (pintype "passive"))
      (node (ref "U4") (pin "81") (pinfunction "P3_5_81") (pintype "bidirectional"))
    )
    (net (code "100") (name "P3_06") (class "Default")
      (node (ref "J12") (pin "4") (pinfunction "4_4") (pintype "passive"))
      (node (ref "U4") (pin "80") (pinfunction "P3_6_80") (pintype "bidirectional"))
    )
    (net (code "101") (name "P3_07") (class "Default")
      (node (ref "J12") (pin "5") (pinfunction "5_5") (pintype "passive"))
      (node (ref "U4") (pin "79") (pinfunction "P3_7_79") (pintype "bidirectional"))
    )
    (net (code "102") (name "P3_09") (class "Default")
      (node (ref "J12") (pin "6") (pinfunction "6_6") (pintype "passive"))
      (node (ref "U4") (pin "77") (pinfunction "P3_9_77") (pintype "bidirectional"))
    )
    (net (code "103") (name "P3_10") (class "Default")
      (node (ref "J12") (pin "7") (pinfunction "7_7") (pintype "passive"))
      (node (ref "U4") (pin "76") (pinfunction "P3_10_76") (pintype "bidirectional"))
    )
    (net (code "104") (name "P3_11") (class "Default")
      (node (ref "J12") (pin "8") (pinfunction "8_8") (pintype "passive"))
      (node (ref "U4") (pin "75") (pinfunction "P3_11_75") (pintype "bidirectional"))
    )
    (net (code "105") (name "P3_12") (class "Default")
      (node (ref "J12") (pin "9") (pinfunction "9_9") (pintype "passive"))
      (node (ref "U4") (pin "74") (pinfunction "P3_12_74") (pintype "bidirectional"))
    )
    (net (code "106") (name "P5_11") (class "Default")
      (node (ref "J7") (pin "7") (pinfunction "7_7") (pintype "passive"))
      (node (ref "U4") (pin "176") (pinfunction "P5_11_176") (pintype "bidirectional"))
    )
    (net (code "107") (name "P5_12") (class "Default")
      (node (ref "J7") (pin "8") (pinfunction "8_8") (pintype "passive"))
      (node (ref "U4") (pin "175") (pinfunction "P5_12_175") (pintype "bidirectional"))
    )
    (net (code "108") (name "P5_13") (class "Default")
      (node (ref "J7") (pin "5") (pinfunction "5_5") (pintype "passive"))
      (node (ref "U4") (pin "174") (pinfunction "P5_13_174") (pintype "bidirectional"))
    )
    (net (code "109") (name "P6_00") (class "Default")
      (node (ref "J10") (pin "P$13") (pinfunction "P$13_P$13") (pintype "bidirectional"))
      (node (ref "U4") (pin "122") (pinfunction "P6_0_122") (pintype "bidirectional"))
    )
    (net (code "110") (name "P6_01") (class "Default")
      (node (ref "J10") (pin "P$14") (pinfunction "P$14_P$14") (pintype "bidirectional"))
      (node (ref "U4") (pin "121") (pinfunction "P6_1_121") (pintype "bidirectional"))
    )
    (net (code "111") (name "P6_02") (class "Default")
      (node (ref "J10") (pin "P$15") (pinfunction "P$15_P$15") (pintype "bidirectional"))
      (node (ref "U4") (pin "120") (pinfunction "P6_2_120") (pintype "bidirectional"))
    )
    (net (code "112") (name "P6_03") (class "Default")
      (node (ref "J10") (pin "P$16") (pinfunction "P$16_P$16") (pintype "bidirectional"))
      (node (ref "U4") (pin "119") (pinfunction "P6_3_119") (pintype "bidirectional"))
    )
    (net (code "113") (name "P6_04") (class "Default")
      (node (ref "J10") (pin "P$17") (pinfunction "P$17_P$17") (pintype "bidirectional"))
      (node (ref "U4") (pin "118") (pinfunction "P6_4_118") (pintype "bidirectional"))
    )
    (net (code "114") (name "P6_05") (class "Default")
      (node (ref "J10") (pin "P$18") (pinfunction "P$18_P$18") (pintype "bidirectional"))
      (node (ref "U4") (pin "117") (pinfunction "P6_5_117") (pintype "bidirectional"))
    )
    (net (code "115") (name "P6_06") (class "Default")
      (node (ref "J10") (pin "P$19") (pinfunction "P$19_P$19") (pintype "bidirectional"))
      (node (ref "U4") (pin "116") (pinfunction "P6_6_116") (pintype "bidirectional"))
    )
    (net (code "116") (name "P6_07") (class "Default")
      (node (ref "J10") (pin "P$20") (pinfunction "P$20_P$20") (pintype "bidirectional"))
      (node (ref "U4") (pin "115") (pinfunction "P6_7_115") (pintype "bidirectional"))
    )
    (net (code "117") (name "P6_08") (class "Default")
      (node (ref "J10") (pin "P$33") (pinfunction "P$33_P$33") (pintype "bidirectional"))
      (node (ref "U4") (pin "99") (pinfunction "P6_8_99") (pintype "bidirectional"))
    )
    (net (code "118") (name "P6_09") (class "Default")
      (node (ref "J10") (pin "P$32") (pinfunction "P$32_P$32") (pintype "bidirectional"))
      (node (ref "U4") (pin "100") (pinfunction "P6_9_100") (pintype "bidirectional"))
    )
    (net (code "119") (name "P6_10") (class "Default")
      (node (ref "J10") (pin "P$31") (pinfunction "P$31_P$31") (pintype "bidirectional"))
      (node (ref "U4") (pin "101") (pinfunction "P6_10_101") (pintype "bidirectional"))
    )
    (net (code "120") (name "P6_11") (class "Default")
      (node (ref "J10") (pin "P$30") (pinfunction "P$30_P$30") (pintype "bidirectional"))
      (node (ref "U4") (pin "102") (pinfunction "P6_11_102") (pintype "bidirectional"))
    )
    (net (code "121") (name "P6_12") (class "Default")
      (node (ref "J10") (pin "P$29") (pinfunction "P$29_P$29") (pintype "bidirectional"))
      (node (ref "U4") (pin "103") (pinfunction "P6_12_103") (pintype "bidirectional"))
    )
    (net (code "122") (name "P6_13") (class "Default")
      (node (ref "J10") (pin "P$28") (pinfunction "P$28_P$28") (pintype "bidirectional"))
      (node (ref "U4") (pin "104") (pinfunction "P6_13_104") (pintype "bidirectional"))
    )
    (net (code "123") (name "P6_14") (class "Default")
      (node (ref "J10") (pin "P$27") (pinfunction "P$27_P$27") (pintype "bidirectional"))
      (node (ref "U4") (pin "105") (pinfunction "P6_14_105") (pintype "bidirectional"))
    )
    (net (code "124") (name "P6_15") (class "Default")
      (node (ref "J10") (pin "P$26") (pinfunction "P$26_P$26") (pintype "bidirectional"))
      (node (ref "U4") (pin "106") (pinfunction "P6_15_106") (pintype "bidirectional"))
    )
    (net (code "125") (name "P7_06") (class "Default")
      (node (ref "U4") (pin "14") (pinfunction "P7_6_14") (pintype "bidirectional"))
    )
    (net (code "126") (name "P7_07") (class "Default")
      (node (ref "U4") (pin "15") (pinfunction "P7_7_15") (pintype "bidirectional"))
    )
    (net (code "127") (name "P8_00") (class "Default")
      (node (ref "J10") (pin "P$4") (pinfunction "P$4_P$4") (pintype "bidirectional"))
      (node (ref "U4") (pin "133") (pinfunction "P8_0_133") (pintype "bidirectional"))
    )
    (net (code "128") (name "P8_01") (class "Default")
      (node (ref "J10") (pin "P$3") (pinfunction "P$3_P$3") (pintype "bidirectional"))
      (node (ref "U4") (pin "134") (pinfunction "P8_1_134") (pintype "bidirectional"))
    )
    (net (code "129") (name "P8_02") (class "Default")
      (node (ref "J10") (pin "P$2") (pinfunction "P$2_P$2") (pintype "bidirectional"))
      (node (ref "U4") (pin "135") (pinfunction "P8_2_135") (pintype "bidirectional"))
    )
    (net (code "130") (name "P8_03") (class "Default")
      (node (ref "J8") (pin "2") (pinfunction "2_2") (pintype "passive"))
      (node (ref "U4") (pin "136") (pinfunction "P8_3_136") (pintype "bidirectional"))
    )
    (net (code "131") (name "P8_04") (class "Default")
      (node (ref "J8") (pin "1") (pinfunction "1_1") (pintype "passive"))
      (node (ref "U4") (pin "137") (pinfunction "P8_4_137") (pintype "bidirectional"))
    )
    (net (code "132") (name "P8_05") (class "Default")
      (node (ref "J7") (pin "6") (pinfunction "6_6") (pintype "passive"))
      (node (ref "U4") (pin "173") (pinfunction "P8_5_173") (pintype "bidirectional"))
    )
    (net (code "133") (name "P9_05") (class "Default")
      (node (ref "J12") (pin "10") (pinfunction "10_10") (pintype "passive"))
      (node (ref "U4") (pin "73") (pinfunction "P9_5_73") (pintype "bidirectional"))
    )
    (net (code "134") (name "P9_06") (class "Default")
      (node (ref "J16") (pin "9") (pinfunction "9_9") (pintype "passive"))
      (node (ref "R10") (pin "P$2") (pinfunction "2_P$2") (pintype "passive"))
      (node (ref "U4") (pin "72") (pinfunction "P9_6_72") (pintype "bidirectional"))
    )
    (net (code "135") (name "P9_07") (class "Default")
      (node (ref "J16") (pin "7") (pinfunction "7_7") (pintype "passive"))
      (node (ref "R9") (pin "P$2") (pinfunction "2_P$2") (pintype "passive"))
      (node (ref "U4") (pin "71") (pinfunction "P9_7_71") (pintype "bidirectional"))
    )
    (net (code "136") (name "P9_08") (class "Default")
      (node (ref "J16") (pin "5") (pinfunction "5_5") (pintype "passive"))
      (node (ref "R8") (pin "P$2") (pinfunction "2_P$2") (pintype "passive"))
      (node (ref "U4") (pin "70") (pinfunction "P9_8_70") (pintype "bidirectional"))
    )
    (net (code "137") (name "PA_00") (class "Default")
      (node (ref "J10") (pin "P$21") (pinfunction "P$21_P$21") (pintype "bidirectional"))
      (node (ref "U4") (pin "114") (pinfunction "PA_0_114") (pintype "bidirectional"))
    )
    (net (code "138") (name "PA_01") (class "Default")
      (node (ref "J10") (pin "P$22") (pinfunction "P$22_P$22") (pintype "bidirectional"))
      (node (ref "U4") (pin "113") (pinfunction "PA_1_113") (pintype "bidirectional"))
    )
    (net (code "139") (name "PA_08") (class "Default")
      (node (ref "J10") (pin "P$25") (pinfunction "P$25_P$25") (pintype "bidirectional"))
      (node (ref "U4") (pin "107") (pinfunction "PA_8_107") (pintype "bidirectional"))
    )
    (net (code "140") (name "PA_09") (class "Default")
      (node (ref "J10") (pin "P$24") (pinfunction "P$24_P$24") (pintype "bidirectional"))
      (node (ref "U4") (pin "108") (pinfunction "PA_9_108") (pintype "bidirectional"))
    )
    (net (code "141") (name "PA_10") (class "Default")
      (node (ref "J10") (pin "P$23") (pinfunction "P$23_P$23") (pintype "bidirectional"))
      (node (ref "U4") (pin "109") (pinfunction "PA_10_109") (pintype "bidirectional"))
    )
    (net (code "142") (name "R51") (class "Default")
      (node (ref "J4") (pin "12") (pinfunction "YHI_12") (pintype "bidirectional"))
      (node (ref "R23") (pin "P$1") (pinfunction "1_P$1") (pintype "passive"))
    )
    (net (code "143") (name "R52") (class "Default")
      (node (ref "J4") (pin "9") (pinfunction "GHI_9") (pintype "bidirectional"))
      (node (ref "R24") (pin "P$1") (pinfunction "1_P$1") (pintype "passive"))
    )
    (net (code "144") (name "RELAY_0") (class "Default")
      (node (ref "RYS6") (pin "P$1") (pinfunction "1_P$1") (pintype "passive"))
      (node (ref "U4") (pin "59") (pinfunction "P9_1_59") (pintype "bidirectional"))
    )
    (net (code "145") (name "RELAY_1") (class "Default")
      (node (ref "RZS3") (pin "P$1") (pinfunction "1_P$1") (pintype "passive"))
      (node (ref "U4") (pin "58") (pinfunction "P9_0_58") (pintype "bidirectional"))
    )
    (net (code "146") (name "RELAY_2") (class "Default")
      (node (ref "RYS5") (pin "P$1") (pinfunction "1_P$1") (pintype "passive"))
      (node (ref "U4") (pin "57") (pinfunction "P3_15_57") (pintype "bidirectional"))
    )
    (net (code "147") (name "RELAY_3") (class "Default")
      (node (ref "RXS3") (pin "P$1") (pinfunction "1_P$1") (pintype "passive"))
      (node (ref "U4") (pin "56") (pinfunction "P3_14_56") (pintype "bidirectional"))
    )
    (net (code "148") (name "RELAY_4") (class "Default")
      (node (ref "RYS16") (pin "P$1") (pinfunction "1_P$1") (pintype "passive"))
      (node (ref "U4") (pin "55") (pinfunction "P3_13_55") (pintype "bidirectional"))
    )
    (net (code "149") (name "RELAY_5") (class "Default")
      (node (ref "RZS8") (pin "P$1") (pinfunction "1_P$1") (pintype "passive"))
      (node (ref "U4") (pin "52") (pinfunction "P2_4_52") (pintype "bidirectional"))
    )
    (net (code "150") (name "RELAY_6") (class "Default")
      (node (ref "RYS15") (pin "P$1") (pinfunction "1_P$1") (pintype "passive"))
      (node (ref "U4") (pin "51") (pinfunction "P2_5_51") (pintype "bidirectional"))
    )
    (net (code "151") (name "RELAY_7") (class "Default")
      (node (ref "RXS8") (pin "P$1") (pinfunction "1_P$1") (pintype "passive"))
      (node (ref "U4") (pin "50") (pinfunction "P2_6_50") (pintype "bidirectional"))
    )
    (net (code "152") (name "RESET") (class "Default")
      (node (ref "C57") (pin "P$1") (pinfunction "1_P$1") (pintype "passive"))
      (node (ref "J11") (pin "9") (pinfunction "9_9") (pintype "passive"))
      (node (ref "R18") (pin "P$1") (pinfunction "1_P$1") (pintype "passive"))
      (node (ref "U4") (pin "67") (pinfunction "RES#_67") (pintype "bidirectional"))
    )
    (net (code "153") (name "REXT") (class "Default")
      (node (ref "C47") (pin "P$1") (pinfunction "1_P$1") (pintype "passive"))
      (node (ref "R25") (pin "P$2") (pinfunction "2_P$2") (pintype "passive"))
      (node (ref "U3") (pin "9") (pinfunction "REXT_9") (pintype "input"))
    )
    (net (code "154") (name "RXD0") (class "Default")
      (node (ref "R31") (pin "P$2") (pinfunction "2_P$2") (pintype "passive"))
      (node (ref "U3") (pin "13") (pinfunction "RXD0_13") (pintype "bidirectional"))
    )
    (net (code "155") (name "RXD1") (class "Default")
      (node (ref "R30") (pin "P$2") (pinfunction "2_P$2") (pintype "passive"))
      (node (ref "U3") (pin "12") (pinfunction "RXD1_12") (pintype "bidirectional"))
    )
    (net (code "156") (name "RXER") (class "Default")
      (node (ref "R32") (pin "P$2") (pinfunction "2_P$2") (pintype "passive"))
      (node (ref "U3") (pin "17") (pinfunction "RXER_17") (pintype "bidirectional"))
    )
    (net (code "157") (name "RXM") (class "Default")
      (node (ref "J4") (pin "6") (pinfunction "RD-_6") (pintype "bidirectional"))
      (node (ref "U3") (pin "3") (pinfunction "RXM_3") (pintype "bidirectional"))
    )
    (net (code "158") (name "RXP") (class "Default")
      (node (ref "J4") (pin "3") (pinfunction "RD+_3") (pintype "bidirectional"))
      (node (ref "U3") (pin "4") (pinfunction "RXP_4") (pintype "bidirectional"))
    )
    (net (code "159") (name "SD1_CD") (class "Default")
      (node (ref "J9") (pin "10") (pinfunction "CD_SWITCH2_10") (pintype "bidirectional"))
      (node (ref "U4") (pin "146") (pinfunction "P5_6/AN019_146") (pintype "bidirectional"))
    )
    (net (code "160") (name "SD1_CLK") (class "Default")
      (node (ref "J9") (pin "5") (pinfunction "CLOCK_5") (pintype "bidirectional"))
      (node (ref "U4") (pin "140") (pinfunction "P5_0/AN016_140") (pintype "bidirectional"))
    )
    (net (code "161") (name "SD1_CMD") (class "Default")
      (node (ref "J9") (pin "3") (pinfunction "COMMAND/RESPONSE_3") (pintype "bidirectional"))
      (node (ref "U4") (pin "141") (pinfunction "P5_1/AN116_141") (pintype "bidirectional"))
    )
    (net (code "162") (name "SD1_DAT0") (class "Default")
      (node (ref "J9") (pin "7") (pinfunction "DATA_LINE[BIT_0]_7") (pintype "bidirectional"))
      (node (ref "U4") (pin "142") (pinfunction "P5_2/AN017_142") (pintype "bidirectional"))
    )
    (net (code "163") (name "SD1_DAT1") (class "Default")
      (node (ref "J9") (pin "8") (pinfunction "DATA_LINE[BIT_1]_8") (pintype "bidirectional"))
      (node (ref "U4") (pin "143") (pinfunction "P5_3/AN117_143") (pintype "bidirectional"))
    )
    (net (code "164") (name "SD1_DAT2") (class "Default")
      (node (ref "J9") (pin "1") (pinfunction "DATA_LINE[BIT_2]_1") (pintype "bidirectional"))
      (node (ref "U4") (pin "144") (pinfunction "P5_4/AN018_144") (pintype "bidirectional"))
    )
    (net (code "165") (name "SD1_DAT3") (class "Default")
      (node (ref "J9") (pin "2") (pinfunction "CARD_DETECT/DATA_LINE[BIT_3]_2") (pintype "bidirectional"))
      (node (ref "U4") (pin "145") (pinfunction "P5_5/AN118_145") (pintype "bidirectional"))
    )
    (net (code "166") (name "SD1_WP") (class "Default")
      (node (ref "J9") (pin "9") (pinfunction "CD_SWITCH1_9") (pintype "bidirectional"))
      (node (ref "U4") (pin "147") (pinfunction "P5_7/AN119_147") (pintype "bidirectional"))
    )
    (net (code "167") (name "TCK") (class "Default")
      (node (ref "J11") (pin "7") (pinfunction "7_7") (pintype "passive"))
      (node (ref "U4") (pin "88") (pinfunction "P3_0_88") (pintype "bidirectional"))
    )
    (net (code "168") (name "TDI") (class "Default")
      (node (ref "J11") (pin "1") (pinfunction "1_1") (pintype "passive"))
      (node (ref "U4") (pin "91") (pinfunction "P1_10_91") (pintype "bidirectional"))
    )
    (net (code "169") (name "TDO") (class "Default")
      (node (ref "J11") (pin "3") (pinfunction "3_3") (pintype "passive"))
      (node (ref "U4") (pin "90") (pinfunction "P1_9_90") (pintype "bidirectional"))
    )
    (net (code "170") (name "TMS") (class "Default")
      (node (ref "J11") (pin "5") (pinfunction "5_5") (pintype "passive"))
      (node (ref "U4") (pin "89") (pinfunction "P1_8_89") (pintype "bidirectional"))
    )
    (net (code "171") (name "TXM") (class "Default")
      (node (ref "J4") (pin "2") (pinfunction "TD-_2") (pintype "bidirectional"))
      (node (ref "U3") (pin "5") (pinfunction "TXM_5") (pintype "bidirectional"))
    )
    (net (code "172") (name "TXP") (class "Default")
      (node (ref "J4") (pin "1") (pinfunction "TD+_1") (pintype "bidirectional"))
      (node (ref "U3") (pin "6") (pinfunction "TXP_6") (pintype "bidirectional"))
    )
    (net (code "173") (name "USBHS_FAULT") (class "Default")
      (node (ref "R12") (pin "P$1") (pinfunction "1_P$1") (pintype "passive"))
      (node (ref "U2") (pin "3") (pinfunction "FLG_3") (pintype "input"))
      (node (ref "U4") (pin "78") (pinfunction "P3_8_78") (pintype "bidirectional"))
    )
    (net (code "174") (name "USBHS_N") (class "Default")
      (node (ref "J3") (pin "D-") (pinfunction "D-_D-") (pintype "bidirectional"))
      (node (ref "U4") (pin "31") (pinfunction "USBHS_DM_31") (pintype "bidirectional"))
    )
    (net (code "175") (name "USBHS_P") (class "Default")
      (node (ref "J3") (pin "D+") (pinfunction "D+_D+") (pintype "bidirectional"))
      (node (ref "U4") (pin "32") (pinfunction "USBHS_DP_32") (pintype "bidirectional"))
    )
    (net (code "176") (name "USBHS_VBUS") (class "Default")
      (node (ref "C11") (pin "P$1") (pinfunction "1_P$1") (pintype "passive"))
      (node (ref "C15") (pin "1") (pinfunction "1_1") (pintype "passive"))
      (node (ref "J3") (pin "VBUS") (pinfunction "VBUS_VBUS") (pintype "power_in"))
      (node (ref "U2") (pin "5") (pinfunction "OUT_5") (pintype "input"))
      (node (ref "U4") (pin "17") (pinfunction "PB_1_17") (pintype "bidirectional"))
    )
    (net (code "177") (name "USBHS_VBUSEN") (class "Default")
      (node (ref "R1") (pin "P$1") (pinfunction "1_P$1") (pintype "passive"))
      (node (ref "U2") (pin "1") (pinfunction "EN_1") (pintype "input"))
    )
    (net (code "178") (name "USB_N") (class "Default")
      (node (ref "R5") (pin "P$1") (pinfunction "1_P$1") (pintype "passive"))
      (node (ref "U4") (pin "46") (pinfunction "USB_DM_46") (pintype "bidirectional"))
    )
    (net (code "179") (name "USB_P") (class "Default")
      (node (ref "R6") (pin "P$1") (pinfunction "1_P$1") (pintype "passive"))
      (node (ref "U4") (pin "47") (pinfunction "USB_DP_47") (pintype "bidirectional"))
    )
    (net (code "180") (name "USB_VBUS_B") (class "Default")
      (node (ref "R4") (pin "P$1") (pinfunction "1_P$1") (pintype "passive"))
      (node (ref "U4") (pin "44") (pinfunction "P4_7_44") (pintype "bidirectional"))
    )
    (net (code "181") (name "VCL_F(FLASH)") (class "Default")
      (node (ref "C36") (pin "P$2") (pinfunction "2_P$2") (pintype "passive"))
      (node (ref "U4") (pin "112") (pinfunction "VCL_F(FLASH)_112") (pintype "bidirectional"))
    )
    (net (code "182") (name "VDD") (class "Default")
      (node (ref "C1") (pin "P$2") (pinfunction "2_P$2") (pintype "passive"))
      (node (ref "C10") (pin "P$2") (pinfunction "2_P$2") (pintype "passive"))
      (node (ref "C13") (pin "P$2") (pinfunction "2_P$2") (pintype "passive"))
      (node (ref "C14") (pin "P$2") (pinfunction "2_P$2") (pintype "passive"))
      (node (ref "C2") (pin "P$2") (pinfunction "2_P$2") (pintype "passive"))
      (node (ref "C30") (pin "P$2") (pinfunction "2_P$2") (pintype "passive"))
      (node (ref "C32") (pin "P$1") (pinfunction "1_P$1") (pintype "passive"))
      (node (ref "C33") (pin "P$1") (pinfunction "1_P$1") (pintype "passive"))
      (node (ref "C34") (pin "P$1") (pinfunction "1_P$1") (pintype "passive"))
      (node (ref "C35") (pin "P$1") (pinfunction "1_P$1") (pintype "passive"))
      (node (ref "C48") (pin "1") (pinfunction "1_1") (pintype "passive"))
      (node (ref "C49") (pin "P$1") (pinfunction "1_P$1") (pintype "passive"))
      (node (ref "C54") (pin "P$2") (pinfunction "2_P$2") (pintype "passive"))
      (node (ref "C55") (pin "P$2") (pinfunction "2_P$2") (pintype "passive"))
      (node (ref "C56") (pin "P$2") (pinfunction "2_P$2") (pintype "passive"))
      (node (ref "C58") (pin "P$1") (pinfunction "1_P$1") (pintype "passive"))
      (node (ref "C59") (pin "P$1") (pinfunction "1_P$1") (pintype "passive"))
      (node (ref "C60") (pin "P$1") (pinfunction "1_P$1") (pintype "passive"))
      (node (ref "C61") (pin "P$2") (pinfunction "2_P$2") (pintype "passive"))
      (node (ref "FB2/2") (pin "1") (pinfunction "P$1_1") (pintype "bidirectional"))
      (node (ref "J11") (pin "2") (pinfunction "2_2") (pintype "passive"))
      (node (ref "J11") (pin "4") (pinfunction "4_4") (pintype "passive"))
      (node (ref "J9") (pin "4") (pinfunction "SUPPLY_VOLTAGE_4") (pintype "power_in"))
      (node (ref "L3") (pin "2") (pinfunction "P$2_2") (pintype "bidirectional"))
      (node (ref "R10") (pin "P$1") (pinfunction "1_P$1") (pintype "passive"))
      (node (ref "R11") (pin "P$1") (pinfunction "1_P$1") (pintype "passive"))
      (node (ref "R13") (pin "P$2") (pinfunction "2_P$2") (pintype "passive"))
      (node (ref "R14") (pin "P$1") (pinfunction "1_P$1") (pintype "passive"))
      (node (ref "R18") (pin "P$2") (pinfunction "2_P$2") (pintype "passive"))
      (node (ref "R2") (pin "P$1") (pinfunction "1_P$1") (pintype "passive"))
      (node (ref "R20") (pin "P$1") (pinfunction "1_P$1") (pintype "passive"))
      (node (ref "R21") (pin "P$1") (pinfunction "1_P$1") (pintype "passive"))
      (node (ref "R23") (pin "P$2") (pinfunction "2_P$2") (pintype "passive"))
      (node (ref "R24") (pin "P$2") (pinfunction "2_P$2") (pintype "passive"))
      (node (ref "R26") (pin "P$2") (pinfunction "2_P$2") (pintype "passive"))
      (node (ref "R27") (pin "P$2") (pinfunction "2_P$2") (pintype "passive"))
      (node (ref "R28") (pin "P$2") (pinfunction "2_P$2") (pintype "passive"))
      (node (ref "R29") (pin "P$2") (pinfunction "2_P$2") (pintype "passive"))
      (node (ref "R3") (pin "P$1") (pinfunction "1_P$1") (pintype "passive"))
      (node (ref "R8") (pin "P$1") (pinfunction "1_P$1") (pintype "passive"))
      (node (ref "R9") (pin "P$1") (pinfunction "1_P$1") (pintype "passive"))
      (node (ref "U3") (pin "14") (pinfunction "VDDIO_14") (pintype "power_in"))
      (node (ref "U4") (pin "110") (pinfunction "VCC(IO)5_110") (pintype "bidirectional"))
      (node (ref "U4") (pin "123") (pinfunction "VCC(IO)6_123") (pintype "bidirectional"))
      (node (ref "U4") (pin "138") (pinfunction "VCC(IO)7_138") (pintype "bidirectional"))
      (node (ref "U4") (pin "149") (pinfunction "VCC(IO)8_149") (pintype "bidirectional"))
      (node (ref "U4") (pin "154") (pinfunction "VREFH_154") (pintype "bidirectional"))
      (node (ref "U4") (pin "155") (pinfunction "AVCC0_155") (pintype "bidirectional"))
      (node (ref "U4") (pin "158") (pinfunction "VREFH0_158") (pintype "bidirectional"))
      (node (ref "U4") (pin "171") (pinfunction "VCC(IO)9_171") (pintype "bidirectional"))
      (node (ref "U4") (pin "25") (pinfunction "VCC1_25") (pintype "bidirectional"))
      (node (ref "U4") (pin "26") (pinfunction "AVCC_SUBHS_26") (pintype "bidirectional"))
      (node (ref "U4") (pin "34") (pinfunction "VCC_USBHS_34") (pintype "bidirectional"))
      (node (ref "U4") (pin "48") (pinfunction "VCC_USB_48") (pintype "bidirectional"))
      (node (ref "U4") (pin "61") (pinfunction "VCC(IO)2_61") (pintype "bidirectional"))
      (node (ref "U4") (pin "84") (pinfunction "VCC(IO)3_84") (pintype "bidirectional"))
      (node (ref "U4") (pin "97") (pinfunction "VCC(IO)4_97") (pintype "bidirectional"))
    )
    (net (code "183") (name "VDD5") (class "Default")
      (node (ref "C5") (pin "P$1") (pinfunction "1_P$1") (pintype "passive"))
      (node (ref "C8") (pin "P$1") (pinfunction "1_P$1") (pintype "passive"))
      (node (ref "J1") (pin "5") (pinfunction "5_5") (pintype "passive"))
      (node (ref "J1") (pin "6") (pinfunction "6_6") (pintype "passive"))
      (node (ref "R1") (pin "P$2") (pinfunction "2_P$2") (pintype "passive"))
      (node (ref "R12") (pin "P$2") (pinfunction "2_P$2") (pintype "passive"))
      (node (ref "U2") (pin "4") (pinfunction "VIN_4") (pintype "input"))
    )
    (net (code "184") (name "VDD12") (class "Default")
      (node (ref "J1") (pin "7") (pinfunction "7_7") (pintype "passive"))
      (node (ref "J1") (pin "8") (pinfunction "8_8") (pintype "passive"))
    )
    (net (code "185") (name "VDDIN") (class "Default")
      (node (ref "J1") (pin "3") (pinfunction "3_3") (pintype "passive"))
      (node (ref "J1") (pin "4") (pinfunction "4_4") (pintype "passive"))
      (node (ref "L3") (pin "1") (pinfunction "P$1_1") (pintype "bidirectional"))
    )
    (net (code "186") (name "VDD_1.2") (class "Default")
      (node (ref "C45") (pin "P$1") (pinfunction "1_P$1") (pintype "passive"))
      (node (ref "C46") (pin "P$1") (pinfunction "1_P$1") (pintype "passive"))
      (node (ref "U3") (pin "1") (pinfunction "VDD_1.2_1") (pintype "power_in"))
    )
    (net (code "187") (name "XCIN") (class "Default")
      (node (ref "C50") (pin "P$1") (pinfunction "1_P$1") (pintype "passive"))
      (node (ref "U4") (pin "20") (pinfunction "XCIN_20") (pintype "bidirectional"))
      (node (ref "X3") (pin "P$1") (pinfunction "P$1_P$1") (pintype "bidirectional"))
    )
    (net (code "188") (name "XCOUT") (class "Default")
      (node (ref "C51") (pin "P$1") (pinfunction "1_P$1") (pintype "passive"))
      (node (ref "U4") (pin "21") (pinfunction "XCOUT_21") (pintype "bidirectional"))
      (node (ref "X3") (pin "P$2") (pinfunction "P$2_P$2") (pintype "bidirectional"))
    )
    (net (code "189") (name "XII") (class "Default")
      (node (ref "C42") (pin "P$1") (pinfunction "1_P$1") (pintype "passive"))
      (node (ref "U$3") (pin "1") (pinfunction "1_1") (pintype "bidirectional"))
      (node (ref "U3") (pin "8") (pinfunction "XI_8") (pintype "input"))
    )
    (net (code "190") (name "XOO") (class "Default")
      (node (ref "C41") (pin "P$1") (pinfunction "1_P$1") (pintype "passive"))
      (node (ref "U$3") (pin "3") (pinfunction "3_3") (pintype "bidirectional"))
      (node (ref "U3") (pin "7") (pinfunction "XO_7") (pintype "output"))
    )
    (net (code "191") (name "XTAL1") (class "Default")
      (node (ref "C52") (pin "P$1") (pinfunction "1_P$1") (pintype "passive"))
      (node (ref "U4") (pin "23") (pinfunction "P2_13/XTAL_23") (pintype "bidirectional"))
      (node (ref "X4") (pin "1") (pinfunction "1_1") (pintype "bidirectional"))
    )
    (net (code "192") (name "XTAL2") (class "Default")
      (node (ref "C53") (pin "P$1") (pinfunction "1_P$1") (pintype "passive"))
      (node (ref "U4") (pin "24") (pinfunction "P2_12/EXTAL_24") (pintype "bidirectional"))
      (node (ref "X4") (pin "3") (pinfunction "3_3") (pintype "bidirectional"))
    )
    (net (code "193") (name "unconnected-(U4-VBAT-Pad18)") (class "Default")
      (node (ref "U4") (pin "18") (pinfunction "VBAT_18") (pintype "bidirectional"))
    )
  )
)
